# zx80_SD_12_smd_build006_8_STM32.net
KiCad netlist of a schematic drawn in EAGLE
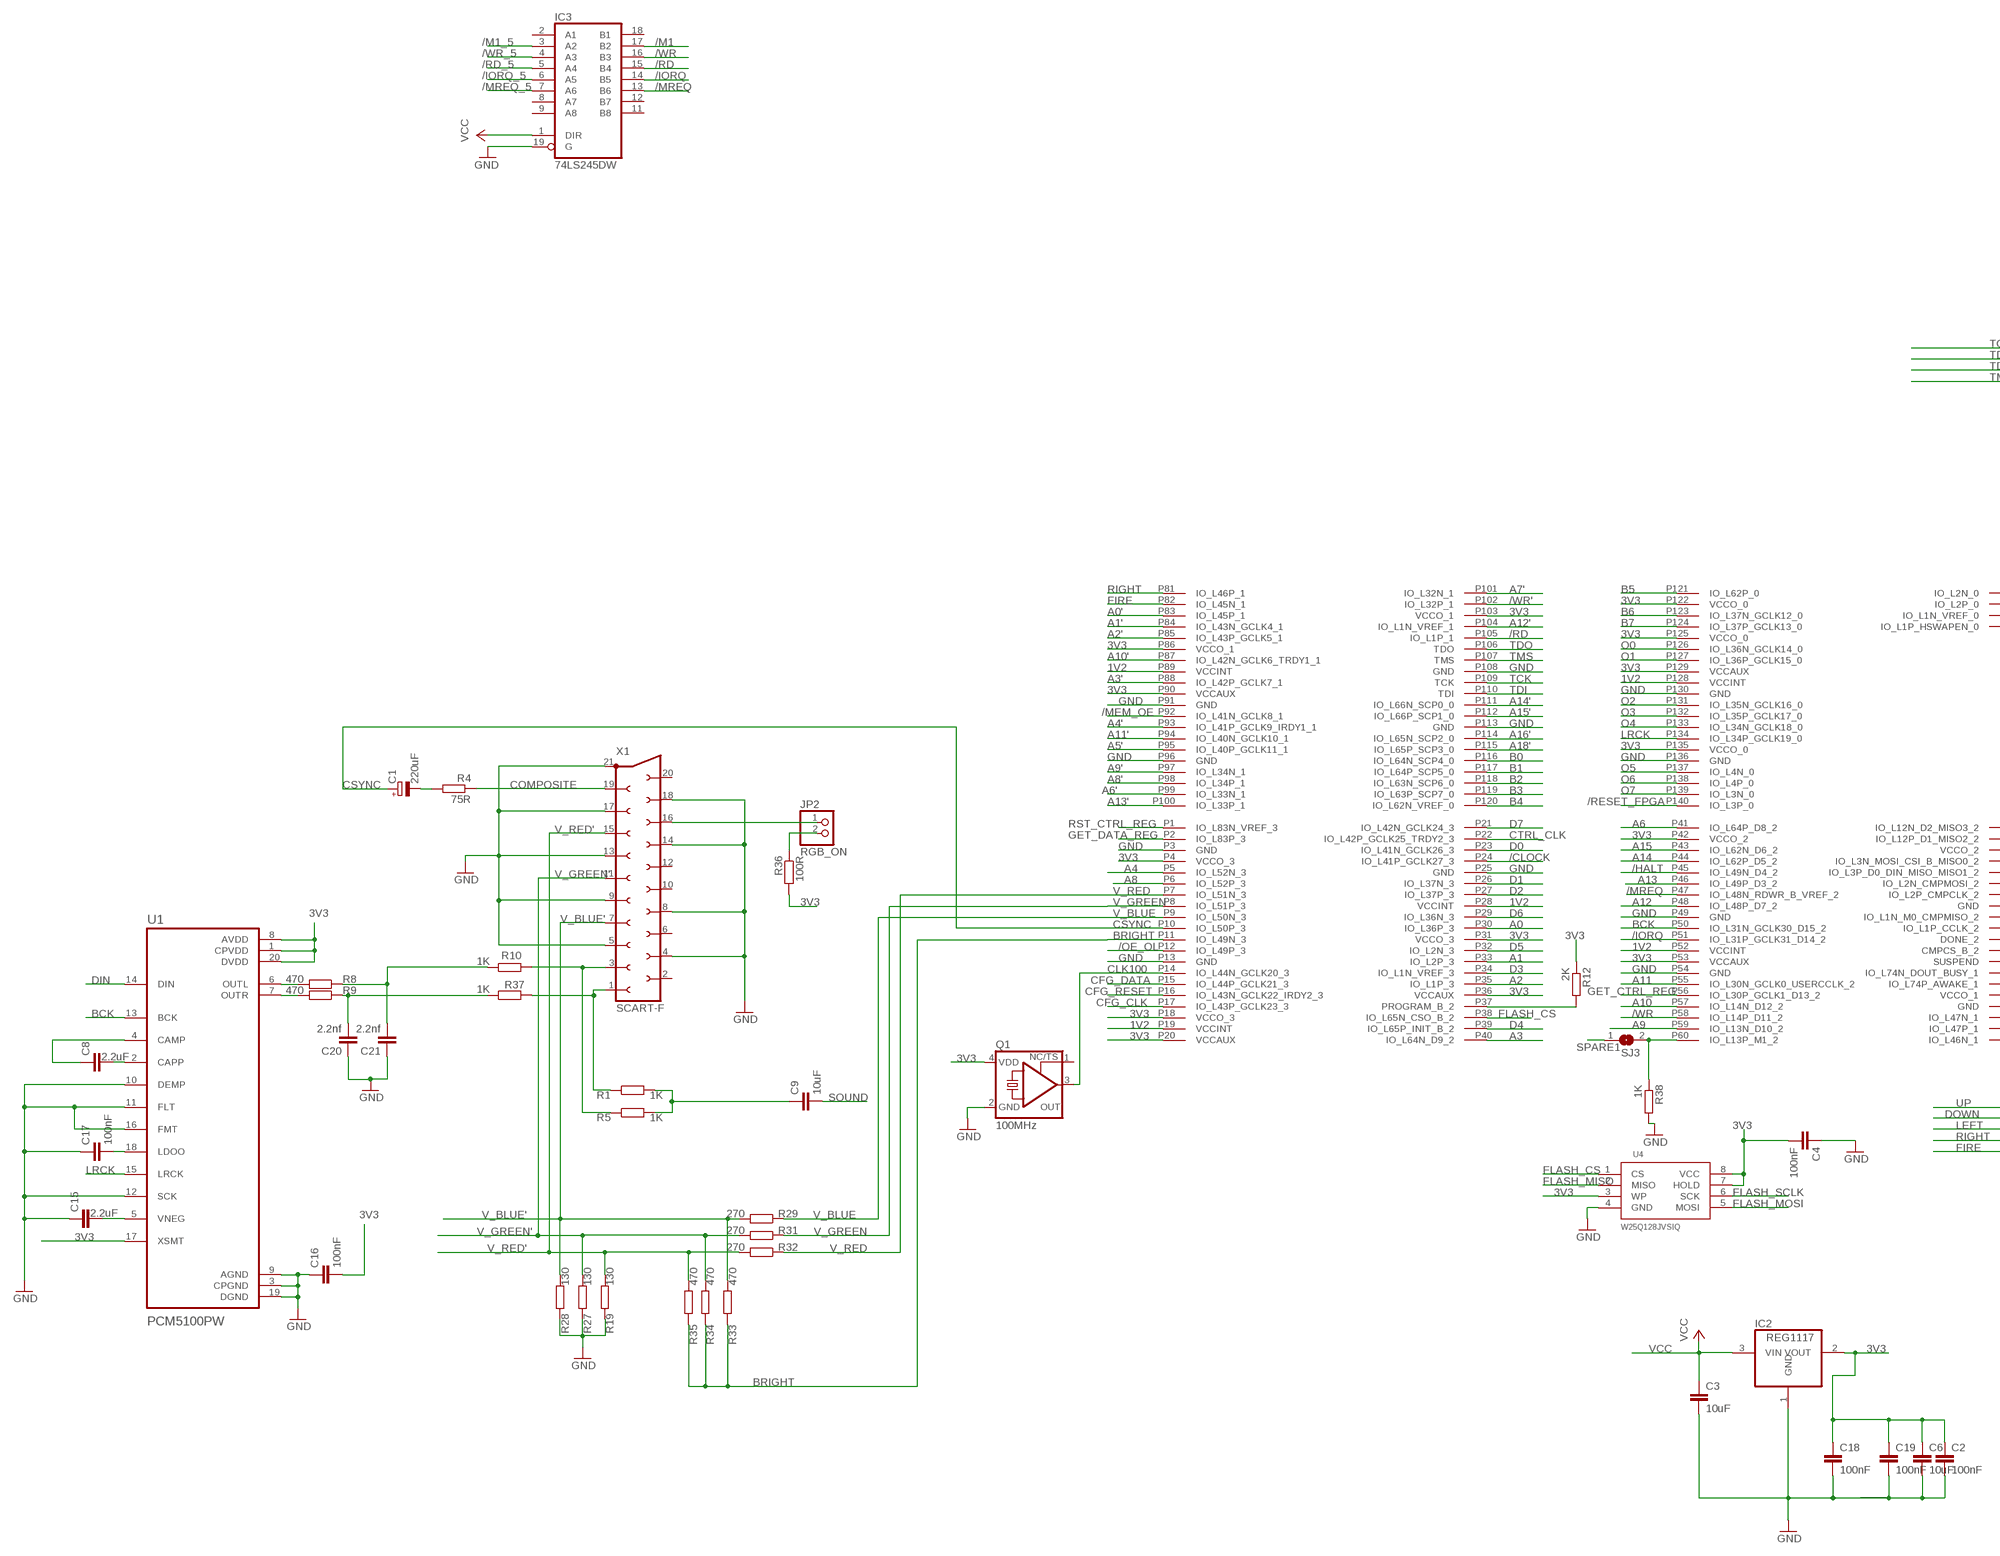
[diagram p0: schematic, sheet 1, part 1 of 2]
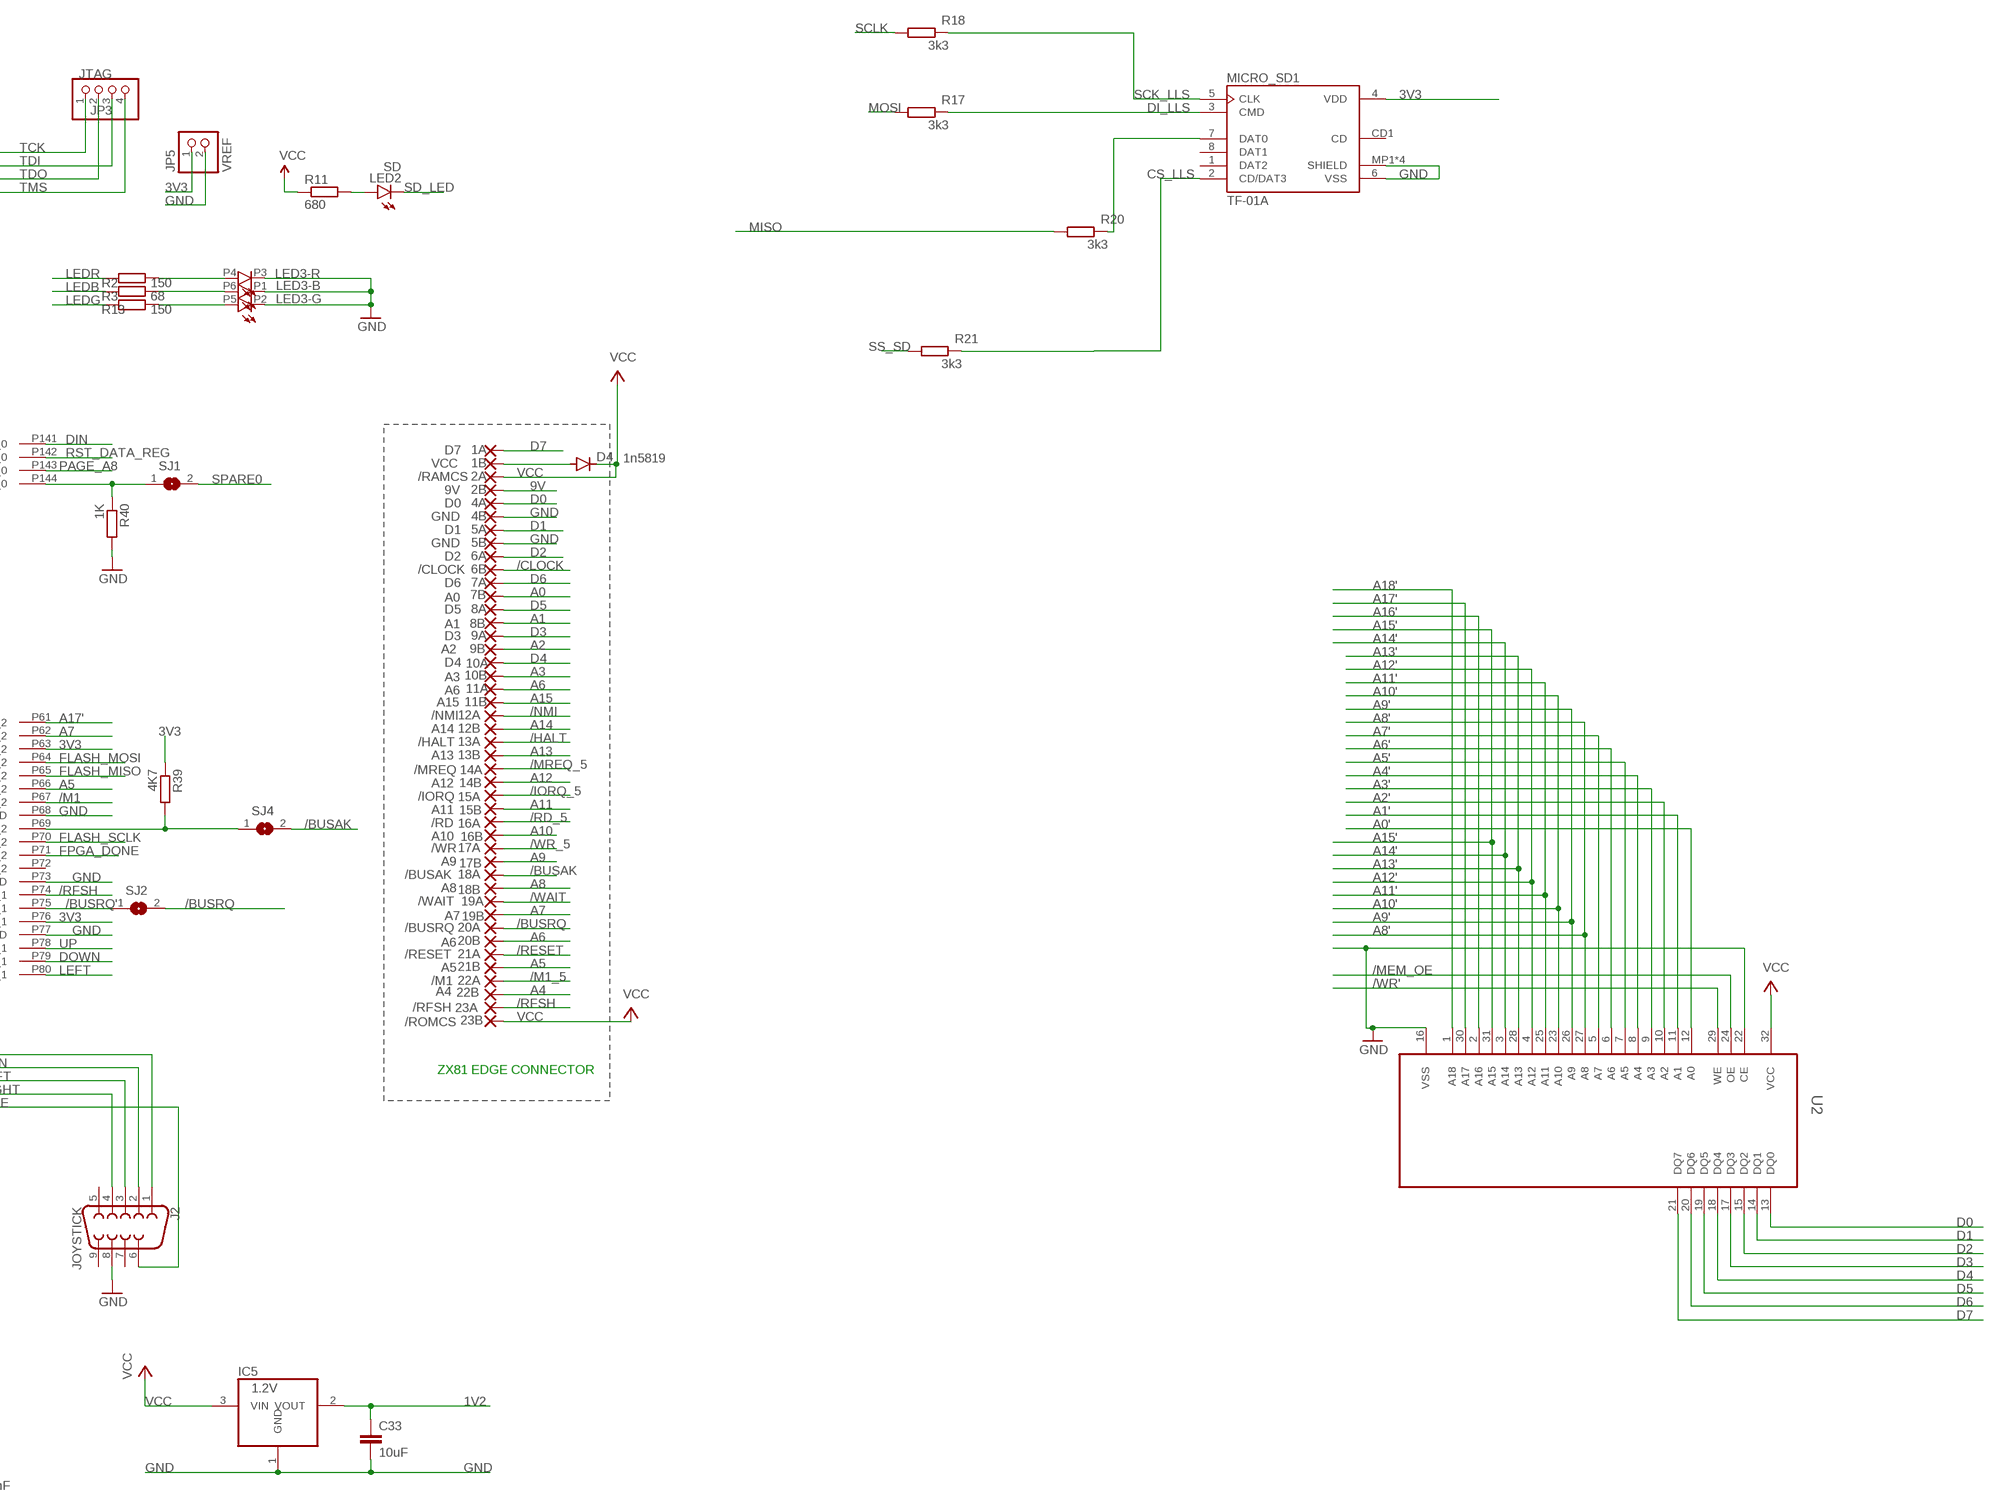
[diagram p1: schematic, sheet 1, part 2 of 2]
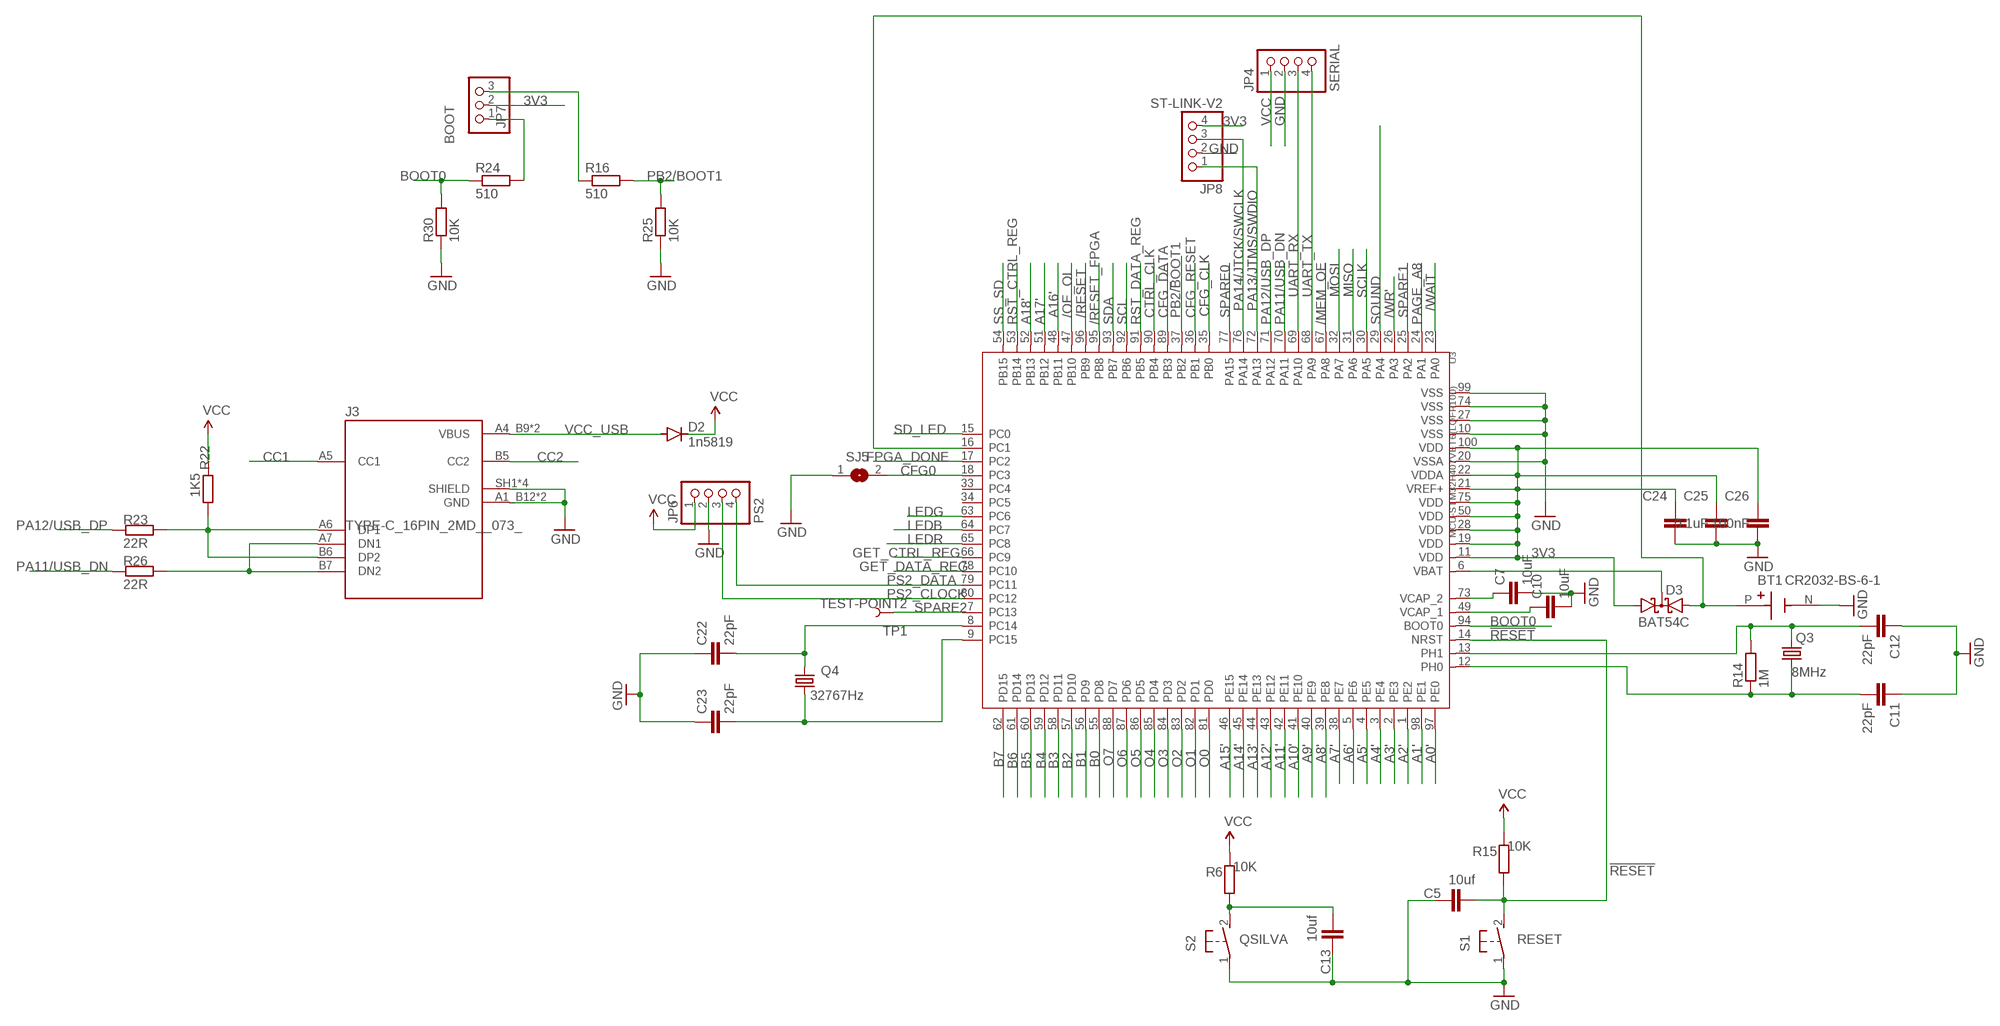
[diagram p2: schematic, sheet 2]

(export (version "E")
  (design (tool "Eeschema 10.0.6"))
  (components
    (comp (ref "1A")
      (value "D7")
      (footprint "eagle-import:EDGEPIN")
      (libsource (lib "eagle-import") (part "SMD2EDGEPIN"))
    )
    (comp (ref "1B")
      (value "VCC")
      (footprint "eagle-import:EDGEPIN")
      (libsource (lib "eagle-import") (part "SMD2EDGEPIN"))
    )
    (comp (ref "2A")
      (value "/RAMCS")
      (footprint "eagle-import:EDGEPIN")
      (libsource (lib "eagle-import") (part "SMD2EDGEPIN"))
    )
    (comp (ref "2B")
      (value "9V")
      (footprint "eagle-import:EDGEPIN")
      (libsource (lib "eagle-import") (part "SMD2EDGEPIN"))
    )
    (comp (ref "4A")
      (value "D0")
      (footprint "eagle-import:EDGEPIN")
      (libsource (lib "eagle-import") (part "SMD2EDGEPIN"))
    )
    (comp (ref "4B")
      (value "GND")
      (footprint "eagle-import:EDGEPIN")
      (libsource (lib "eagle-import") (part "SMD2EDGEPIN"))
    )
    (comp (ref "5A")
      (value "D1")
      (footprint "eagle-import:EDGEPIN")
      (libsource (lib "eagle-import") (part "SMD2EDGEPIN"))
    )
    (comp (ref "5B")
      (value "GND")
      (footprint "eagle-import:EDGEPIN")
      (libsource (lib "eagle-import") (part "SMD2EDGEPIN"))
    )
    (comp (ref "6A")
      (value "D2")
      (footprint "eagle-import:EDGEPIN")
      (libsource (lib "eagle-import") (part "SMD2EDGEPIN"))
    )
    (comp (ref "6B")
      (value "/CLOCK")
      (footprint "eagle-import:EDGEPIN")
      (libsource (lib "eagle-import") (part "SMD2EDGEPIN"))
    )
    (comp (ref "7A")
      (value "D6")
      (footprint "eagle-import:EDGEPIN")
      (libsource (lib "eagle-import") (part "SMD2EDGEPIN"))
    )
    (comp (ref "7B")
      (value "A0")
      (footprint "eagle-import:EDGEPIN")
      (libsource (lib "eagle-import") (part "SMD2EDGEPIN"))
    )
    (comp (ref "8A")
      (value "D5")
      (footprint "eagle-import:EDGEPIN")
      (libsource (lib "eagle-import") (part "SMD2EDGEPIN"))
    )
    (comp (ref "8B")
      (value "A1")
      (footprint "eagle-import:EDGEPIN")
      (libsource (lib "eagle-import") (part "SMD2EDGEPIN"))
    )
    (comp (ref "9A")
      (value "D3")
      (footprint "eagle-import:EDGEPIN")
      (libsource (lib "eagle-import") (part "SMD2EDGEPIN"))
    )
    (comp (ref "9B")
      (value "A2")
      (footprint "eagle-import:EDGEPIN")
      (libsource (lib "eagle-import") (part "SMD2EDGEPIN"))
    )
    (comp (ref "10A")
      (value "D4")
      (footprint "eagle-import:EDGEPIN")
      (libsource (lib "eagle-import") (part "SMD2EDGEPIN"))
    )
    (comp (ref "10B")
      (value "A3")
      (footprint "eagle-import:EDGEPIN")
      (libsource (lib "eagle-import") (part "SMD2EDGEPIN"))
    )
    (comp (ref "11A")
      (value "A6")
      (footprint "eagle-import:EDGEPIN")
      (libsource (lib "eagle-import") (part "SMD2EDGEPIN"))
    )
    (comp (ref "11B")
      (value "A15")
      (footprint "eagle-import:EDGEPIN")
      (libsource (lib "eagle-import") (part "SMD2EDGEPIN"))
    )
    (comp (ref "12A")
      (value "/NMI")
      (footprint "eagle-import:EDGEPIN")
      (libsource (lib "eagle-import") (part "SMD2EDGEPIN"))
    )
    (comp (ref "12B")
      (value "A14")
      (footprint "eagle-import:EDGEPIN")
      (libsource (lib "eagle-import") (part "SMD2EDGEPIN"))
    )
    (comp (ref "13A")
      (value "/HALT")
      (footprint "eagle-import:EDGEPIN")
      (libsource (lib "eagle-import") (part "SMD2EDGEPIN"))
    )
    (comp (ref "13B")
      (value "A13")
      (footprint "eagle-import:EDGEPIN")
      (libsource (lib "eagle-import") (part "SMD2EDGEPIN"))
    )
    (comp (ref "14A")
      (value "/MREQ")
      (footprint "eagle-import:EDGEPIN")
      (libsource (lib "eagle-import") (part "SMD2EDGEPIN"))
    )
    (comp (ref "14B")
      (value "A12")
      (footprint "eagle-import:EDGEPIN")
      (libsource (lib "eagle-import") (part "SMD2EDGEPIN"))
    )
    (comp (ref "15A")
      (value "/IORQ")
      (footprint "eagle-import:EDGEPIN")
      (libsource (lib "eagle-import") (part "SMD2EDGEPIN"))
    )
    (comp (ref "15B")
      (value "A11")
      (footprint "eagle-import:EDGEPIN")
      (libsource (lib "eagle-import") (part "SMD2EDGEPIN"))
    )
    (comp (ref "16A")
      (value "/RD")
      (footprint "eagle-import:EDGEPIN")
      (libsource (lib "eagle-import") (part "SMD2EDGEPIN"))
    )
    (comp (ref "16B")
      (value "A10")
      (footprint "eagle-import:EDGEPIN")
      (libsource (lib "eagle-import") (part "SMD2EDGEPIN"))
    )
    (comp (ref "17A")
      (value "/WR")
      (footprint "eagle-import:EDGEPIN")
      (libsource (lib "eagle-import") (part "SMD2EDGEPIN"))
    )
    (comp (ref "17B")
      (value "A9")
      (footprint "eagle-import:EDGEPIN")
      (libsource (lib "eagle-import") (part "SMD2EDGEPIN"))
    )
    (comp (ref "18A")
      (value "/BUSAK")
      (footprint "eagle-import:EDGEPIN")
      (libsource (lib "eagle-import") (part "SMD2EDGEPIN"))
    )
    (comp (ref "18B")
      (value "A8")
      (footprint "eagle-import:EDGEPIN")
      (libsource (lib "eagle-import") (part "SMD2EDGEPIN"))
    )
    (comp (ref "19A")
      (value "/WAIT")
      (footprint "eagle-import:EDGEPIN")
      (libsource (lib "eagle-import") (part "SMD2EDGEPIN"))
    )
    (comp (ref "19B")
      (value "A7")
      (footprint "eagle-import:EDGEPIN")
      (libsource (lib "eagle-import") (part "SMD2EDGEPIN"))
    )
    (comp (ref "20A")
      (value "/BUSRQ")
      (footprint "eagle-import:EDGEPIN")
      (libsource (lib "eagle-import") (part "SMD2EDGEPIN"))
    )
    (comp (ref "20B")
      (value "A6")
      (footprint "eagle-import:EDGEPIN")
      (libsource (lib "eagle-import") (part "SMD2EDGEPIN"))
    )
    (comp (ref "21A")
      (value "/RESET")
      (footprint "eagle-import:EDGEPIN")
      (libsource (lib "eagle-import") (part "SMD2EDGEPIN"))
    )
    (comp (ref "21B")
      (value "A5")
      (footprint "eagle-import:EDGEPIN")
      (libsource (lib "eagle-import") (part "SMD2EDGEPIN"))
    )
    (comp (ref "22A")
      (value "/M1")
      (footprint "eagle-import:EDGEPIN")
      (libsource (lib "eagle-import") (part "SMD2EDGEPIN"))
    )
    (comp (ref "22B")
      (value "A4")
      (footprint "eagle-import:EDGEPIN")
      (libsource (lib "eagle-import") (part "SMD2EDGEPIN"))
    )
    (comp (ref "23A")
      (value "/RFSH")
      (footprint "eagle-import:EDGEPIN")
      (libsource (lib "eagle-import") (part "SMD2EDGEPIN"))
    )
    (comp (ref "23B")
      (value "/ROMCS")
      (footprint "eagle-import:EDGEPIN")
      (libsource (lib "eagle-import") (part "SMD2EDGEPIN"))
    )
    (comp (ref "C1")
      (value "220uF")
      (footprint "eagle-import:UD-6,3X7,7_NICHICON")
      (libsource (lib "eagle-import") (part "CPOL-EUUD-6,3X7,7"))
    )
    (comp (ref "C2")
      (value "100nF")
      (footprint "eagle-import:C0402K")
      (libsource (lib "eagle-import") (part "C-EUC0402K"))
    )
    (comp (ref "C3")
      (value "10uF")
      (footprint "eagle-import:C0402K")
      (libsource (lib "eagle-import") (part "C-EUC0402K"))
    )
    (comp (ref "C4")
      (value "100nF")
      (footprint "eagle-import:C0402K")
      (libsource (lib "eagle-import") (part "C-EUC0402K"))
    )
    (comp (ref "C6")
      (value "10uF")
      (footprint "eagle-import:C0402K")
      (libsource (lib "eagle-import") (part "C-EUC0402K"))
    )
    (comp (ref "C8")
      (value "2.2uF")
      (footprint "eagle-import:C0402K")
      (libsource (lib "eagle-import") (part "C-EUC0402K"))
    )
    (comp (ref "C9")
      (value "10uF")
      (footprint "eagle-import:C0402K")
      (libsource (lib "eagle-import") (part "C-EUC0402K"))
    )
    (comp (ref "C15")
      (value "2.2uF")
      (footprint "eagle-import:C0402K")
      (libsource (lib "eagle-import") (part "C-EUC0402K"))
    )
    (comp (ref "C16")
      (value "100nF")
      (footprint "eagle-import:C0402K")
      (libsource (lib "eagle-import") (part "C-EUC0402K"))
    )
    (comp (ref "C17")
      (value "100nF")
      (footprint "eagle-import:C0402K")
      (libsource (lib "eagle-import") (part "C-EUC0402K"))
    )
    (comp (ref "C18")
      (value "100nF")
      (footprint "eagle-import:C0402K")
      (libsource (lib "eagle-import") (part "C-EUC0402K"))
    )
    (comp (ref "C19")
      (value "100nF")
      (footprint "eagle-import:C0402K")
      (libsource (lib "eagle-import") (part "C-EUC0402K"))
    )
    (comp (ref "C20")
      (value "2.2nf")
      (footprint "eagle-import:C0603K")
      (libsource (lib "eagle-import") (part "C-EUC0603K"))
    )
    (comp (ref "C21")
      (value "2.2nf")
      (footprint "eagle-import:C0603K")
      (libsource (lib "eagle-import") (part "C-EUC0603K"))
    )
    (comp (ref "C33")
      (value "10uF")
      (footprint "eagle-import:C0402K")
      (libsource (lib "eagle-import") (part "C-EUC0402K"))
    )
    (comp (ref "D4")
      (value "1n5819")
      (footprint "eagle-import:SOD323-W")
      (libsource (lib "eagle-import") (part "DIODE-SOD323-W"))
    )
    (comp (ref "IC2")
      (value "REG1117")
      (footprint "eagle-import:SOT223")
      (libsource (lib "eagle-import") (part "REG1117"))
    )
    (comp (ref "IC3")
      (value "74LS245DW")
      (footprint "eagle-import:SO20W")
      (libsource (lib "eagle-import") (part "74245DWLS"))
    )
    (comp (ref "IC5")
      (value "1.2V")
      (footprint "eagle-import:SOT223")
      (fields (field (name "MPN") "REG1117"))
      (libsource (lib "eagle-import") (part "REG1117"))
    )
    (comp (ref "J2")
      (value "JOYSTICK")
      (footprint "eagle-import:DB9_MALE")
      (libsource (lib "eagle-import") (part "DB9MALE"))
    )
    (comp (ref "JP2")
      (value "RGB_ON")
      (footprint "eagle-import:1X02")
      (libsource (lib "eagle-import") (part "PINHD-1X2"))
    )
    (comp (ref "JP3")
      (value "JTAG")
      (footprint "eagle-import:1X04")
      (libsource (lib "eagle-import") (part "PINHD-1X4"))
    )
    (comp (ref "JP5")
      (value "VREF")
      (footprint "eagle-import:1X02")
      (libsource (lib "eagle-import") (part "PINHD-1X2"))
    )
    (comp (ref "LED2")
      (value "SD")
      (footprint "eagle-import:CHIPLED_0805")
      (libsource (lib "eagle-import") (part "LEDCHIPLED_0805"))
    )
    (comp (ref "LED3")
      (value "STATUS")
      (footprint "eagle-import:3535-PLCC6")
      (libsource (lib "eagle-import") (part "3535RGB3535RGB"))
    )
    (comp (ref "MICRO_SD1")
      (value "TF-01A")
      (footprint "eagle-import:TF-01A")
      (fields (field (name "MF") "HRO Electronics Co., Ltd."))
      (libsource (lib "eagle-import") (part "TF-01A"))
    )
    (comp (ref "Q1")
      (value "100MHz")
      (footprint "eagle-import:3.2X2.5_KXO-V96")
      (libsource (lib "eagle-import") (part "KXO-PXO/XO-V96"))
    )
    (comp (ref "R1")
      (value "1K")
      (footprint "eagle-import:R0402")
      (libsource (lib "eagle-import") (part "R-EU_R0402"))
    )
    (comp (ref "R2")
      (value "150")
      (footprint "eagle-import:R0402")
      (libsource (lib "eagle-import") (part "R-EU_R0402"))
    )
    (comp (ref "R3")
      (value "68")
      (footprint "eagle-import:R0402")
      (libsource (lib "eagle-import") (part "R-EU_R0402"))
    )
    (comp (ref "R4")
      (value "75R")
      (footprint "eagle-import:R0402")
      (libsource (lib "eagle-import") (part "R-EU_R0402"))
    )
    (comp (ref "R5")
      (value "1K")
      (footprint "eagle-import:R0402")
      (libsource (lib "eagle-import") (part "R-EU_R0402"))
    )
    (comp (ref "R8")
      (value "470")
      (footprint "eagle-import:R0402")
      (libsource (lib "eagle-import") (part "R-EU_R0402"))
    )
    (comp (ref "R9")
      (value "470")
      (footprint "eagle-import:R0402")
      (libsource (lib "eagle-import") (part "R-EU_R0402"))
    )
    (comp (ref "R10")
      (value "1K")
      (footprint "eagle-import:R0402")
      (libsource (lib "eagle-import") (part "R-EU_R0402"))
    )
    (comp (ref "R11")
      (value "680")
      (footprint "eagle-import:R0402")
      (libsource (lib "eagle-import") (part "R-EU_R0402"))
    )
    (comp (ref "R12")
      (value "2K")
      (footprint "eagle-import:R0402")
      (libsource (lib "eagle-import") (part "R-EU_R0402"))
    )
    (comp (ref "R13")
      (value "150")
      (footprint "eagle-import:R0402")
      (libsource (lib "eagle-import") (part "R-EU_R0402"))
    )
    (comp (ref "R17")
      (value "3k3")
      (footprint "eagle-import:R0402")
      (libsource (lib "eagle-import") (part "R-EU_R0402"))
    )
    (comp (ref "R18")
      (value "3k3")
      (footprint "eagle-import:R0402")
      (libsource (lib "eagle-import") (part "R-EU_R0402"))
    )
    (comp (ref "R19")
      (value "130")
      (footprint "eagle-import:R0402")
      (libsource (lib "eagle-import") (part "R-EU_R0402"))
    )
    (comp (ref "R20")
      (value "3k3")
      (footprint "eagle-import:R0402")
      (libsource (lib "eagle-import") (part "R-EU_R0402"))
    )
    (comp (ref "R21")
      (value "3k3")
      (footprint "eagle-import:R0402")
      (libsource (lib "eagle-import") (part "R-EU_R0402"))
    )
    (comp (ref "R27")
      (value "130")
      (footprint "eagle-import:R0402")
      (libsource (lib "eagle-import") (part "R-EU_R0402"))
    )
    (comp (ref "R28")
      (value "130")
      (footprint "eagle-import:R0402")
      (libsource (lib "eagle-import") (part "R-EU_R0402"))
    )
    (comp (ref "R29")
      (value "270")
      (footprint "eagle-import:R0402")
      (libsource (lib "eagle-import") (part "R-EU_R0402"))
    )
    (comp (ref "R31")
      (value "270")
      (footprint "eagle-import:R0402")
      (libsource (lib "eagle-import") (part "R-EU_R0402"))
    )
    (comp (ref "R32")
      (value "270")
      (footprint "eagle-import:R0402")
      (libsource (lib "eagle-import") (part "R-EU_R0402"))
    )
    (comp (ref "R33")
      (value "470")
      (footprint "eagle-import:R0402")
      (libsource (lib "eagle-import") (part "R-EU_R0402"))
    )
    (comp (ref "R34")
      (value "470")
      (footprint "eagle-import:R0402")
      (libsource (lib "eagle-import") (part "R-EU_R0402"))
    )
    (comp (ref "R35")
      (value "470")
      (footprint "eagle-import:R0402")
      (libsource (lib "eagle-import") (part "R-EU_R0402"))
    )
    (comp (ref "R36")
      (value "100R")
      (footprint "eagle-import:R0402")
      (libsource (lib "eagle-import") (part "R-EU_R0402"))
    )
    (comp (ref "R37")
      (value "1K")
      (footprint "eagle-import:R0402")
      (libsource (lib "eagle-import") (part "R-EU_R0402"))
    )
    (comp (ref "R38")
      (value "1K")
      (footprint "eagle-import:R0402")
      (libsource (lib "eagle-import") (part "R-EU_R0402"))
    )
    (comp (ref "R39")
      (value "4K7")
      (footprint "eagle-import:R0402")
      (libsource (lib "eagle-import") (part "R-EU_R0402"))
    )
    (comp (ref "R40")
      (value "1K")
      (footprint "eagle-import:R0402")
      (libsource (lib "eagle-import") (part "R-EU_R0402"))
    )
    (comp (ref "SJ1") (value "SJ") (footprint "eagle-import:SJ") (libsource (lib "eagle-import") (part "SJ")))
    (comp (ref "SJ2") (value "SJ") (footprint "eagle-import:SJ") (libsource (lib "eagle-import") (part "SJ")))
    (comp (ref "SJ3") (value "SJ") (footprint "eagle-import:SJ") (libsource (lib "eagle-import") (part "SJ")))
    (comp (ref "SJ4") (value "SJ") (footprint "eagle-import:SJ") (libsource (lib "eagle-import") (part "SJ")))
    (comp (ref "U1")
      (value "PCM5100PW")
      (footprint "eagle-import:SOP65P640X120-20N")
      (fields (field (name "MF") "Texas Instruments"))
      (libsource (lib "eagle-import") (part "PCM5100PW"))
    )
    (comp (ref "U2")
      (value "AS6C4008")
      (footprint "eagle-import:SOP32-5")
      (libsource (lib "eagle-import") (part "AS6C4008-55SINSOP5"))
    )
    (comp (ref "U4")
      (value "W25Q128JVSIQ")
      (footprint "eagle-import:SO08-EIAJ")
      (libsource (lib "eagle-import") (part "SPI_FLASH-X25XXSMD1"))
    )
    (comp (ref "U6")
      (value "XC6SLX9-2TQG144C")
      (footprint "eagle-import:TQ144")
      (fields (field (name "MF") "Xilinx Inc."))
      (libsource (lib "eagle-import") (part "XC6SLX9-2TQG144C"))
    )
    (comp (ref "X1")
      (value "SCART-F")
      (footprint "eagle-import:SCART-F")
      (libsource (lib "eagle-import") (part "SCART-F"))
    )
    (comp (ref "BT1")
      (value "CR2032-BS-6-1")
      (footprint "eagle-import:BAT_CR2032-BS-6-1")
      (fields (field (name "MF") "Shenzhen Q&J Electronics Co. Ltd"))
      (libsource (lib "eagle-import") (part "CR2032-BS-6-1"))
    )
    (comp (ref "C5")
      (value "10uf")
      (footprint "eagle-import:C0402K")
      (libsource (lib "eagle-import") (part "C-EUC0402K"))
    )
    (comp (ref "C7")
      (value "10uF")
      (footprint "eagle-import:C0402K")
      (libsource (lib "eagle-import") (part "C-EUC0402K"))
    )
    (comp (ref "C10")
      (value "10uF")
      (footprint "eagle-import:C0402K")
      (libsource (lib "eagle-import") (part "C-EUC0402K"))
    )
    (comp (ref "C11")
      (value "22pF")
      (footprint "eagle-import:C0603")
      (libsource (lib "eagle-import") (part "C-EUC0603"))
    )
    (comp (ref "C12")
      (value "22pF")
      (footprint "eagle-import:C0603")
      (libsource (lib "eagle-import") (part "C-EUC0603"))
    )
    (comp (ref "C13")
      (value "10uf")
      (footprint "eagle-import:C0402K")
      (libsource (lib "eagle-import") (part "C-EUC0402K"))
    )
    (comp (ref "C22")
      (value "22pF")
      (footprint "eagle-import:C0603")
      (libsource (lib "eagle-import") (part "C-EUC0603"))
    )
    (comp (ref "C23")
      (value "22pF")
      (footprint "eagle-import:C0603")
      (libsource (lib "eagle-import") (part "C-EUC0603"))
    )
    (comp (ref "C24")
      (value "0.1uF")
      (footprint "eagle-import:C0402K")
      (libsource (lib "eagle-import") (part "C-EUC0402K"))
    )
    (comp (ref "C25")
      (value "0.1uF")
      (footprint "eagle-import:C0402K")
      (libsource (lib "eagle-import") (part "C-EUC0402K"))
    )
    (comp (ref "C26")
      (value "100nF")
      (footprint "eagle-import:C0402K")
      (libsource (lib "eagle-import") (part "C-EUC0402K"))
    )
    (comp (ref "D2")
      (value "1n5819")
      (footprint "eagle-import:SOD323-W")
      (libsource (lib "eagle-import") (part "DIODE-SOD323-W"))
    )
    (comp (ref "D3")
      (value "BAT54C")
      (footprint "eagle-import:SOT23")
      (libsource (lib "eagle-import") (part "BAT54C"))
    )
    (comp (ref "J3")
      (value "TYPE-C_16PIN_2MD__073_")
      (footprint "eagle-import:SHOUHAN_TYPE-C_16PIN_2MD__073_")
      (fields (field (name "MF") "Shouhan") (field (name "MP") "TYPE-C 16PIN 2MD (073)"))
      (libsource (lib "eagle-import") (part "TYPE-C_16PIN_2MD__073_"))
    )
    (comp (ref "JP4")
      (value "SERIAL")
      (footprint "eagle-import:1X04")
      (libsource (lib "eagle-import") (part "PINHD-1X4"))
    )
    (comp (ref "JP6")
      (value "PS2")
      (footprint "eagle-import:1X04")
      (libsource (lib "eagle-import") (part "PINHD-1X4"))
    )
    (comp (ref "JP7")
      (value "BOOT")
      (footprint "eagle-import:1X03")
      (libsource (lib "eagle-import") (part "PINHD-1X3"))
    )
    (comp (ref "JP8")
      (value "ST-LINK-V2")
      (footprint "eagle-import:1X04")
      (libsource (lib "eagle-import") (part "PINHD-1X4"))
    )
    (comp (ref "Q3")
      (value "8MHz")
      (footprint "eagle-import:3.2X2.5_KX-7")
      (libsource (lib "eagle-import") (part "KX-7"))
    )
    (comp (ref "Q4")
      (value "32767Hz")
      (footprint "eagle-import:3.2X1.5")
      (libsource (lib "eagle-import") (part "KX-327-NHT"))
    )
    (comp (ref "R6")
      (value "10K")
      (footprint "eagle-import:R0402")
      (libsource (lib "eagle-import") (part "R-EU_R0402"))
    )
    (comp (ref "R14")
      (value "1M")
      (footprint "eagle-import:R0402")
      (libsource (lib "eagle-import") (part "R-EU_R0402"))
    )
    (comp (ref "R15")
      (value "10K")
      (footprint "eagle-import:R0402")
      (libsource (lib "eagle-import") (part "R-EU_R0402"))
    )
    (comp (ref "R16")
      (value "510")
      (footprint "eagle-import:R0402")
      (libsource (lib "eagle-import") (part "R-EU_R0402"))
    )
    (comp (ref "R22")
      (value "1K5")
      (footprint "eagle-import:R0402")
      (libsource (lib "eagle-import") (part "R-EU_R0402"))
    )
    (comp (ref "R23")
      (value "22R")
      (footprint "eagle-import:R0402")
      (libsource (lib "eagle-import") (part "R-EU_R0402"))
    )
    (comp (ref "R24")
      (value "510")
      (footprint "eagle-import:R0402")
      (libsource (lib "eagle-import") (part "R-EU_R0402"))
    )
    (comp (ref "R25")
      (value "10K")
      (footprint "eagle-import:R0402")
      (libsource (lib "eagle-import") (part "R-EU_R0402"))
    )
    (comp (ref "R26")
      (value "22R")
      (footprint "eagle-import:R0402")
      (libsource (lib "eagle-import") (part "R-EU_R0402"))
    )
    (comp (ref "R30")
      (value "10K")
      (footprint "eagle-import:R0402")
      (libsource (lib "eagle-import") (part "R-EU_R0402"))
    )
    (comp (ref "S1")
      (value "RESET")
      (footprint "eagle-import:B3F-31XX")
      (fields (field (name "MPN") "B3F-3100"))
      (libsource (lib "eagle-import") (part "31-XX"))
    )
    (comp (ref "S2")
      (value "QSILVA")
      (footprint "eagle-import:B3F-31XX")
      (fields (field (name "MPN") "B3F-3100"))
      (libsource (lib "eagle-import") (part "31-XX"))
    )
    (comp (ref "SJ5")
      (value "SJ")
      (footprint "eagle-import:SJ")
      (libsource (lib "eagle-import") (part "jumper_41245853_SJ"))
    )
    (comp (ref "TP1")
      (value "TEST-POINT2")
      (footprint "eagle-import:PAD.02X.02")
      (libsource (lib "eagle-import") (part "TEST-POINT2"))
    )
    (comp (ref "U3")
      (value "MCU-STM32F407VET6(LQFP100)")
      (footprint "eagle-import:LQFP100-0.5-13.8X13.8MM")
      (fields (field (name "MF") "STMicroelectronics") (field (name "MP") "STM32F407VET6"))
      (libsource (lib "eagle-import") (part "MCU-STM32F407VET6(LQFP100)"))
    )
  )
  (nets
    (net (code "1") (name "1V2") (class "Default")
      (node (ref "C33") (pin "1") (pinfunction "1_1") (pintype "passive"))
      (node (ref "IC5") (pin "2") (pinfunction "VOUT_2") (pintype "output"))
      (node (ref "U6") (pin "P128") (pinfunction "VCCINT_P128") (pintype "bidirectional"))
      (node (ref "U6") (pin "P19") (pinfunction "VCCINT_P19") (pintype "bidirectional"))
      (node (ref "U6") (pin "P28") (pinfunction "VCCINT_P28") (pintype "bidirectional"))
      (node (ref "U6") (pin "P52") (pinfunction "VCCINT_P52") (pintype "bidirectional"))
      (node (ref "U6") (pin "P89") (pinfunction "VCCINT_P89") (pintype "bidirectional"))
    )
    (net (code "2") (name "3V3") (class "Default")
      (node (ref "C16") (pin "2") (pinfunction "2_2") (pintype "passive"))
      (node (ref "C18") (pin "1") (pinfunction "1_1") (pintype "passive"))
      (node (ref "C19") (pin "1") (pinfunction "1_1") (pintype "passive"))
      (node (ref "C2") (pin "1") (pinfunction "1_1") (pintype "passive"))
      (node (ref "C24") (pin "1") (pinfunction "1_1") (pintype "passive"))
      (node (ref "C25") (pin "1") (pinfunction "1_1") (pintype "passive"))
      (node (ref "C26") (pin "1") (pinfunction "1_1") (pintype "passive"))
      (node (ref "C4") (pin "2") (pinfunction "2_2") (pintype "passive"))
      (node (ref "C6") (pin "1") (pinfunction "1_1") (pintype "passive"))
      (node (ref "D3") (pin "1") (pinfunction "A1_1") (pintype "passive"))
      (node (ref "IC2") (pin "2") (pinfunction "VOUT_2") (pintype "output"))
      (node (ref "JP5") (pin "1") (pinfunction "1_1") (pintype "passive"))
      (node (ref "JP7") (pin "2") (pinfunction "2_2") (pintype "passive"))
      (node (ref "JP8") (pin "4") (pinfunction "4_4") (pintype "passive"))
      (node (ref "MICRO_SD1") (pin "4") (pinfunction "VDD_4") (pintype "power_in"))
      (node (ref "Q1") (pin "4") (pinfunction "VDD_4") (pintype "power_in"))
      (node (ref "R12") (pin "1") (pinfunction "1_1") (pintype "passive"))
      (node (ref "R36") (pin "2") (pinfunction "2_2") (pintype "passive"))
      (node (ref "R39") (pin "1") (pinfunction "1_1") (pintype "passive"))
      (node (ref "U1") (pin "1") (pinfunction "CPVDD_1") (pintype "power_in"))
      (node (ref "U1") (pin "17") (pinfunction "XSMT_17") (pintype "bidirectional"))
      (node (ref "U1") (pin "20") (pinfunction "DVDD_20") (pintype "power_in"))
      (node (ref "U1") (pin "8") (pinfunction "AVDD_8") (pintype "power_in"))
      (node (ref "U3") (pin "100") (pinfunction "VDD_100") (pintype "bidirectional"))
      (node (ref "U3") (pin "11") (pinfunction "VDD_11") (pintype "bidirectional"))
      (node (ref "U3") (pin "19") (pinfunction "VDD_19") (pintype "bidirectional"))
      (node (ref "U3") (pin "21") (pinfunction "VREF+_21") (pintype "bidirectional"))
      (node (ref "U3") (pin "22") (pinfunction "VDDA_22") (pintype "bidirectional"))
      (node (ref "U3") (pin "28") (pinfunction "VDD_28") (pintype "bidirectional"))
      (node (ref "U3") (pin "50") (pinfunction "VDD_50") (pintype "bidirectional"))
      (node (ref "U3") (pin "75") (pinfunction "VDD_75") (pintype "bidirectional"))
      (node (ref "U4") (pin "3") (pinfunction "WP_3") (pintype "bidirectional"))
      (node (ref "U4") (pin "7") (pinfunction "HOLD_7") (pintype "bidirectional"))
      (node (ref "U4") (pin "8") (pinfunction "VCC_8") (pintype "power_in"))
      (node (ref "U6") (pin "P103") (pinfunction "VCCO_1_P103") (pintype "bidirectional"))
      (node (ref "U6") (pin "P122") (pinfunction "VCCO_0_P122") (pintype "bidirectional"))
      (node (ref "U6") (pin "P125") (pinfunction "VCCO_0_P125") (pintype "bidirectional"))
      (node (ref "U6") (pin "P129") (pinfunction "VCCAUX_P129") (pintype "bidirectional"))
      (node (ref "U6") (pin "P135") (pinfunction "VCCO_0_P135") (pintype "bidirectional"))
      (node (ref "U6") (pin "P18") (pinfunction "VCCO_3_P18") (pintype "bidirectional"))
      (node (ref "U6") (pin "P20") (pinfunction "VCCAUX_P20") (pintype "bidirectional"))
      (node (ref "U6") (pin "P31") (pinfunction "VCCO_3_P31") (pintype "bidirectional"))
      (node (ref "U6") (pin "P36") (pinfunction "VCCAUX_P36") (pintype "bidirectional"))
      (node (ref "U6") (pin "P4") (pinfunction "VCCO_3_P4") (pintype "bidirectional"))
      (node (ref "U6") (pin "P42") (pinfunction "VCCO_2_P42") (pintype "bidirectional"))
      (node (ref "U6") (pin "P53") (pinfunction "VCCAUX_P53") (pintype "bidirectional"))
      (node (ref "U6") (pin "P63") (pinfunction "VCCO_2_P63") (pintype "bidirectional"))
      (node (ref "U6") (pin "P76") (pinfunction "VCCO_1_P76") (pintype "bidirectional"))
      (node (ref "U6") (pin "P86") (pinfunction "VCCO_1_P86") (pintype "bidirectional"))
      (node (ref "U6") (pin "P90") (pinfunction "VCCAUX_P90") (pintype "bidirectional"))
    )
    (net (code "3") (name "9V") (class "Default")
      (node (ref "2B") (pin "1") (pinfunction "P_1") (pintype "passive"))
    )
    (net (code "4") (name "A0") (class "Default")
      (node (ref "7B") (pin "1") (pinfunction "P_1") (pintype "passive"))
      (node (ref "U6") (pin "P30") (pinfunction "IO_L36P_3_P30") (pintype "bidirectional"))
    )
    (net (code "5") (name "A0'") (class "Default")
      (node (ref "U2") (pin "12") (pinfunction "A0_12") (pintype "input"))
      (node (ref "U3") (pin "97") (pinfunction "PE0_97") (pintype "bidirectional"))
      (node (ref "U6") (pin "P83") (pinfunction "IO_L45P_1_P83") (pintype "bidirectional"))
    )
    (net (code "6") (name "A1") (class "Default")
      (node (ref "8B") (pin "1") (pinfunction "P_1") (pintype "passive"))
      (node (ref "U6") (pin "P33") (pinfunction "IO_L2P_3_P33") (pintype "bidirectional"))
    )
    (net (code "7") (name "A1'") (class "Default")
      (node (ref "U2") (pin "11") (pinfunction "A1_11") (pintype "input"))
      (node (ref "U3") (pin "98") (pinfunction "PE1_98") (pintype "bidirectional"))
      (node (ref "U6") (pin "P84") (pinfunction "IO_L43N_GCLK4_1_P84") (pintype "bidirectional"))
    )
    (net (code "8") (name "A2") (class "Default")
      (node (ref "9B") (pin "1") (pinfunction "P_1") (pintype "passive"))
      (node (ref "U6") (pin "P35") (pinfunction "IO_L1P_3_P35") (pintype "bidirectional"))
    )
    (net (code "9") (name "A2'") (class "Default")
      (node (ref "U2") (pin "10") (pinfunction "A2_10") (pintype "input"))
      (node (ref "U3") (pin "1") (pinfunction "PE2_1") (pintype "bidirectional"))
      (node (ref "U6") (pin "P85") (pinfunction "IO_L43P_GCLK5_1_P85") (pintype "bidirectional"))
    )
    (net (code "10") (name "A3") (class "Default")
      (node (ref "10B") (pin "1") (pinfunction "P_1") (pintype "passive"))
      (node (ref "U6") (pin "P40") (pinfunction "IO_L64N_D9_2_P40") (pintype "bidirectional"))
    )
    (net (code "11") (name "A3'") (class "Default")
      (node (ref "U2") (pin "9") (pinfunction "A3_9") (pintype "input"))
      (node (ref "U3") (pin "2") (pinfunction "PE3_2") (pintype "bidirectional"))
      (node (ref "U6") (pin "P88") (pinfunction "IO_L42P_GCLK7_1_P88") (pintype "bidirectional"))
    )
    (net (code "12") (name "A4") (class "Default")
      (node (ref "22B") (pin "1") (pinfunction "P_1") (pintype "passive"))
      (node (ref "U6") (pin "P5") (pinfunction "IO_L52N_3_P5") (pintype "bidirectional"))
    )
    (net (code "13") (name "A4'") (class "Default")
      (node (ref "U2") (pin "8") (pinfunction "A4_8") (pintype "input"))
      (node (ref "U3") (pin "3") (pinfunction "PE4_3") (pintype "bidirectional"))
      (node (ref "U6") (pin "P93") (pinfunction "IO_L41P_GCLK9_IRDY1_1_P93") (pintype "bidirectional"))
    )
    (net (code "14") (name "A5") (class "Default")
      (node (ref "21B") (pin "1") (pinfunction "P_1") (pintype "passive"))
      (node (ref "U6") (pin "P66") (pinfunction "IO_L2N_CMPMOSI_2_P66") (pintype "bidirectional"))
    )
    (net (code "15") (name "A5'") (class "Default")
      (node (ref "U2") (pin "7") (pinfunction "A5_7") (pintype "input"))
      (node (ref "U3") (pin "4") (pinfunction "PE5_4") (pintype "bidirectional"))
      (node (ref "U6") (pin "P95") (pinfunction "IO_L40P_GCLK11_1_P95") (pintype "bidirectional"))
    )
    (net (code "16") (name "A6") (class "Default")
      (node (ref "11A") (pin "1") (pinfunction "P_1") (pintype "passive"))
      (node (ref "20B") (pin "1") (pinfunction "P_1") (pintype "passive"))
      (node (ref "U6") (pin "P41") (pinfunction "IO_L64P_D8_2_P41") (pintype "bidirectional"))
    )
    (net (code "17") (name "A6'") (class "Default")
      (node (ref "U2") (pin "6") (pinfunction "A6_6") (pintype "input"))
      (node (ref "U3") (pin "5") (pinfunction "PE6_5") (pintype "bidirectional"))
      (node (ref "U6") (pin "P99") (pinfunction "IO_L33N_1_P99") (pintype "bidirectional"))
    )
    (net (code "18") (name "A7") (class "Default")
      (node (ref "19B") (pin "1") (pinfunction "P_1") (pintype "passive"))
      (node (ref "U6") (pin "P62") (pinfunction "IO_L12P_D1_MISO2_2_P62") (pintype "bidirectional"))
    )
    (net (code "19") (name "A7'") (class "Default")
      (node (ref "U2") (pin "5") (pinfunction "A7_5") (pintype "input"))
      (node (ref "U3") (pin "38") (pinfunction "PE7_38") (pintype "bidirectional"))
      (node (ref "U6") (pin "P101") (pinfunction "IO_L32N_1_P101") (pintype "bidirectional"))
    )
    (net (code "20") (name "A8") (class "Default")
      (node (ref "18B") (pin "1") (pinfunction "P_1") (pintype "passive"))
      (node (ref "U6") (pin "P6") (pinfunction "IO_L52P_3_P6") (pintype "bidirectional"))
    )
    (net (code "21") (name "A8'") (class "Default")
      (node (ref "U2") (pin "27") (pinfunction "A8_27") (pintype "input"))
      (node (ref "U3") (pin "39") (pinfunction "PE8_39") (pintype "bidirectional"))
      (node (ref "U6") (pin "P98") (pinfunction "IO_L34P_1_P98") (pintype "bidirectional"))
    )
    (net (code "22") (name "A9") (class "Default")
      (node (ref "17B") (pin "1") (pinfunction "P_1") (pintype "passive"))
      (node (ref "U6") (pin "P59") (pinfunction "IO_L13N_D10_2_P59") (pintype "bidirectional"))
    )
    (net (code "23") (name "A9'") (class "Default")
      (node (ref "U2") (pin "26") (pinfunction "A9_26") (pintype "input"))
      (node (ref "U3") (pin "40") (pinfunction "PE9_40") (pintype "bidirectional"))
      (node (ref "U6") (pin "P97") (pinfunction "IO_L34N_1_P97") (pintype "bidirectional"))
    )
    (net (code "24") (name "A10") (class "Default")
      (node (ref "16B") (pin "1") (pinfunction "P_1") (pintype "passive"))
      (node (ref "U6") (pin "P57") (pinfunction "IO_L14N_D12_2_P57") (pintype "bidirectional"))
    )
    (net (code "25") (name "A10'") (class "Default")
      (node (ref "U2") (pin "23") (pinfunction "A10_23") (pintype "input"))
      (node (ref "U3") (pin "41") (pinfunction "PE10_41") (pintype "bidirectional"))
      (node (ref "U6") (pin "P87") (pinfunction "IO_L42N_GCLK6_TRDY1_1_P87") (pintype "bidirectional"))
    )
    (net (code "26") (name "A11") (class "Default")
      (node (ref "15B") (pin "1") (pinfunction "P_1") (pintype "passive"))
      (node (ref "U6") (pin "P55") (pinfunction "IO_L30N_GCLK0_USERCCLK_2_P55") (pintype "bidirectional"))
    )
    (net (code "27") (name "A11'") (class "Default")
      (node (ref "U2") (pin "25") (pinfunction "A11_25") (pintype "input"))
      (node (ref "U3") (pin "42") (pinfunction "PE11_42") (pintype "bidirectional"))
      (node (ref "U6") (pin "P94") (pinfunction "IO_L40N_GCLK10_1_P94") (pintype "bidirectional"))
    )
    (net (code "28") (name "A12") (class "Default")
      (node (ref "14B") (pin "1") (pinfunction "P_1") (pintype "passive"))
      (node (ref "U6") (pin "P48") (pinfunction "IO_L48P_D7_2_P48") (pintype "bidirectional"))
    )
    (net (code "29") (name "A12'") (class "Default")
      (node (ref "U2") (pin "4") (pinfunction "A12_4") (pintype "input"))
      (node (ref "U3") (pin "43") (pinfunction "PE12_43") (pintype "bidirectional"))
      (node (ref "U6") (pin "P104") (pinfunction "IO_L1N_VREF_1_P104") (pintype "bidirectional"))
    )
    (net (code "30") (name "A13") (class "Default")
      (node (ref "13B") (pin "1") (pinfunction "P_1") (pintype "passive"))
      (node (ref "U6") (pin "P46") (pinfunction "IO_L49P_D3_2_P46") (pintype "bidirectional"))
    )
    (net (code "31") (name "A13'") (class "Default")
      (node (ref "U2") (pin "28") (pinfunction "A13_28") (pintype "input"))
      (node (ref "U3") (pin "44") (pinfunction "PE13_44") (pintype "bidirectional"))
      (node (ref "U6") (pin "P100") (pinfunction "IO_L33P_1_P100") (pintype "bidirectional"))
    )
    (net (code "32") (name "A14") (class "Default")
      (node (ref "12B") (pin "1") (pinfunction "P_1") (pintype "passive"))
      (node (ref "U6") (pin "P44") (pinfunction "IO_L62P_D5_2_P44") (pintype "bidirectional"))
    )
    (net (code "33") (name "A14'") (class "Default")
      (node (ref "U2") (pin "3") (pinfunction "A14_3") (pintype "input"))
      (node (ref "U3") (pin "45") (pinfunction "PE14_45") (pintype "bidirectional"))
      (node (ref "U6") (pin "P111") (pinfunction "IO_L66N_SCP0_0_P111") (pintype "bidirectional"))
    )
    (net (code "34") (name "A15") (class "Default")
      (node (ref "11B") (pin "1") (pinfunction "P_1") (pintype "passive"))
      (node (ref "U6") (pin "P43") (pinfunction "IO_L62N_D6_2_P43") (pintype "bidirectional"))
    )
    (net (code "35") (name "A15'") (class "Default")
      (node (ref "U2") (pin "31") (pinfunction "A15_31") (pintype "input"))
      (node (ref "U3") (pin "46") (pinfunction "PE15_46") (pintype "bidirectional"))
      (node (ref "U6") (pin "P112") (pinfunction "IO_L66P_SCP1_0_P112") (pintype "bidirectional"))
    )
    (net (code "36") (name "A16'") (class "Default")
      (node (ref "U2") (pin "2") (pinfunction "A16_2") (pintype "input"))
      (node (ref "U3") (pin "48") (pinfunction "PB11_48") (pintype "bidirectional"))
      (node (ref "U6") (pin "P114") (pinfunction "IO_L65N_SCP2_0_P114") (pintype "bidirectional"))
    )
    (net (code "37") (name "A17'") (class "Default")
      (node (ref "U2") (pin "30") (pinfunction "A17_30") (pintype "input"))
      (node (ref "U3") (pin "51") (pinfunction "PB12_51") (pintype "bidirectional"))
      (node (ref "U6") (pin "P61") (pinfunction "IO_L12N_D2_MISO3_2_P61") (pintype "bidirectional"))
    )
    (net (code "38") (name "A18'") (class "Default")
      (node (ref "U2") (pin "1") (pinfunction "A18_1") (pintype "input"))
      (node (ref "U3") (pin "52") (pinfunction "PB13_52") (pintype "bidirectional"))
      (node (ref "U6") (pin "P115") (pinfunction "IO_L65P_SCP3_0_P115") (pintype "bidirectional"))
    )
    (net (code "39") (name "B0") (class "Default")
      (node (ref "U3") (pin "55") (pinfunction "PD8_55") (pintype "bidirectional"))
      (node (ref "U6") (pin "P116") (pinfunction "IO_L64N_SCP4_0_P116") (pintype "bidirectional"))
    )
    (net (code "40") (name "B1") (class "Default")
      (node (ref "U3") (pin "56") (pinfunction "PD9_56") (pintype "bidirectional"))
      (node (ref "U6") (pin "P117") (pinfunction "IO_L64P_SCP5_0_P117") (pintype "bidirectional"))
    )
    (net (code "41") (name "B2") (class "Default")
      (node (ref "U3") (pin "57") (pinfunction "PD10_57") (pintype "bidirectional"))
      (node (ref "U6") (pin "P118") (pinfunction "IO_L63N_SCP6_0_P118") (pintype "bidirectional"))
    )
    (net (code "42") (name "B3") (class "Default")
      (node (ref "U3") (pin "58") (pinfunction "PD11_58") (pintype "bidirectional"))
      (node (ref "U6") (pin "P119") (pinfunction "IO_L63P_SCP7_0_P119") (pintype "bidirectional"))
    )
    (net (code "43") (name "B4") (class "Default")
      (node (ref "U3") (pin "59") (pinfunction "PD12_59") (pintype "bidirectional"))
      (node (ref "U6") (pin "P120") (pinfunction "IO_L62N_VREF_0_P120") (pintype "bidirectional"))
    )
    (net (code "44") (name "B5") (class "Default")
      (node (ref "U3") (pin "60") (pinfunction "PD13_60") (pintype "bidirectional"))
      (node (ref "U6") (pin "P121") (pinfunction "IO_L62P_0_P121") (pintype "bidirectional"))
    )
    (net (code "45") (name "B6") (class "Default")
      (node (ref "U3") (pin "61") (pinfunction "PD14_61") (pintype "bidirectional"))
      (node (ref "U6") (pin "P123") (pinfunction "IO_L37N_GCLK12_0_P123") (pintype "bidirectional"))
    )
    (net (code "46") (name "B7") (class "Default")
      (node (ref "U3") (pin "62") (pinfunction "PD15_62") (pintype "bidirectional"))
      (node (ref "U6") (pin "P124") (pinfunction "IO_L37P_GCLK13_0_P124") (pintype "bidirectional"))
    )
    (net (code "47") (name "BCK") (class "Default")
      (node (ref "U1") (pin "13") (pinfunction "BCK_13") (pintype "bidirectional"))
      (node (ref "U6") (pin "P50") (pinfunction "IO_L31N_GCLK30_D15_2_P50") (pintype "bidirectional"))
    )
    (net (code "48") (name "BOOT0") (class "Default")
      (node (ref "R24") (pin "1") (pinfunction "1_1") (pintype "passive"))
      (node (ref "R30") (pin "2") (pinfunction "2_2") (pintype "passive"))
      (node (ref "U3") (pin "94") (pinfunction "BOOT0_94") (pintype "bidirectional"))
    )
    (net (code "49") (name "BRIGHT") (class "Default")
      (node (ref "R33") (pin "1") (pinfunction "1_1") (pintype "passive"))
      (node (ref "R34") (pin "1") (pinfunction "1_1") (pintype "passive"))
      (node (ref "R35") (pin "1") (pinfunction "1_1") (pintype "passive"))
      (node (ref "U6") (pin "P11") (pinfunction "IO_L49N_3_P11") (pintype "bidirectional"))
    )
    (net (code "50") (name "CC1") (class "Default")
      (node (ref "J3") (pin "A5") (pinfunction "CC1_A5") (pintype "bidirectional"))
    )
    (net (code "51") (name "CC2") (class "Default")
      (node (ref "J3") (pin "B5") (pinfunction "CC2_B5") (pintype "bidirectional"))
    )
    (net (code "52") (name "CFG0") (class "Default")
      (node (ref "SJ5") (pin "2") (pinfunction "2_2") (pintype "passive"))
      (node (ref "U3") (pin "18") (pinfunction "PC3_18") (pintype "bidirectional"))
    )
    (net (code "53") (name "CFG_CLK") (class "Default")
      (node (ref "U3") (pin "35") (pinfunction "PB0_35") (pintype "bidirectional"))
      (node (ref "U6") (pin "P17") (pinfunction "IO_L43P_GCLK23_3_P17") (pintype "bidirectional"))
    )
    (net (code "54") (name "CFG_DATA") (class "Default")
      (node (ref "U3") (pin "89") (pinfunction "PB3_89") (pintype "bidirectional"))
      (node (ref "U6") (pin "P15") (pinfunction "IO_L44P_GCLK21_3_P15") (pintype "bidirectional"))
    )
    (net (code "55") (name "CFG_RESET") (class "Default")
      (node (ref "U3") (pin "36") (pinfunction "PB1_36") (pintype "bidirectional"))
      (node (ref "U6") (pin "P16") (pinfunction "IO_L43N_GCLK22_IRDY2_3_P16") (pintype "bidirectional"))
    )
    (net (code "56") (name "CLK100") (class "Default")
      (node (ref "Q1") (pin "3") (pinfunction "OUT_3") (pintype "output"))
      (node (ref "U6") (pin "P14") (pinfunction "IO_L44N_GCLK20_3_P14") (pintype "bidirectional"))
    )
    (net (code "57") (name "COMPOSITE") (class "Default")
      (node (ref "R4") (pin "1") (pinfunction "1_1") (pintype "passive"))
      (node (ref "X1") (pin "19") (pinfunction "19_19") (pintype "passive"))
    )
    (net (code "58") (name "CSYNC") (class "Default")
      (node (ref "C1") (pin "+") (pinfunction "+_+") (pintype "passive"))
      (node (ref "U6") (pin "P10") (pinfunction "IO_L50P_3_P10") (pintype "bidirectional"))
    )
    (net (code "59") (name "CS_LLS") (class "Default")
      (node (ref "MICRO_SD1") (pin "2") (pinfunction "CD/DAT3_2") (pintype "bidirectional"))
      (node (ref "R21") (pin "2") (pinfunction "2_2") (pintype "passive"))
    )
    (net (code "60") (name "CTRL_CLK") (class "Default")
      (node (ref "U3") (pin "90") (pinfunction "PB4_90") (pintype "bidirectional"))
      (node (ref "U6") (pin "P22") (pinfunction "IO_L42P_GCLK25_TRDY2_3_P22") (pintype "bidirectional"))
    )
    (net (code "61") (name "D0") (class "Default")
      (node (ref "4A") (pin "1") (pinfunction "P_1") (pintype "passive"))
      (node (ref "U2") (pin "13") (pinfunction "DQ0_13") (pintype "output"))
      (node (ref "U6") (pin "P23") (pinfunction "IO_L41N_GCLK26_3_P23") (pintype "bidirectional"))
    )
    (net (code "62") (name "D1") (class "Default")
      (node (ref "5A") (pin "1") (pinfunction "P_1") (pintype "passive"))
      (node (ref "U2") (pin "14") (pinfunction "DQ1_14") (pintype "output"))
      (node (ref "U6") (pin "P26") (pinfunction "IO_L37N_3_P26") (pintype "bidirectional"))
    )
    (net (code "63") (name "D2") (class "Default")
      (node (ref "6A") (pin "1") (pinfunction "P_1") (pintype "passive"))
      (node (ref "U2") (pin "15") (pinfunction "DQ2_15") (pintype "output"))
      (node (ref "U6") (pin "P27") (pinfunction "IO_L37P_3_P27") (pintype "bidirectional"))
    )
    (net (code "64") (name "D3") (class "Default")
      (node (ref "9A") (pin "1") (pinfunction "P_1") (pintype "passive"))
      (node (ref "U2") (pin "17") (pinfunction "DQ3_17") (pintype "output"))
      (node (ref "U6") (pin "P34") (pinfunction "IO_L1N_VREF_3_P34") (pintype "bidirectional"))
    )
    (net (code "65") (name "D4") (class "Default")
      (node (ref "10A") (pin "1") (pinfunction "P_1") (pintype "passive"))
      (node (ref "U2") (pin "18") (pinfunction "DQ4_18") (pintype "output"))
      (node (ref "U6") (pin "P39") (pinfunction "IO_L65P_INIT_B_2_P39") (pintype "bidirectional"))
    )
    (net (code "66") (name "D5") (class "Default")
      (node (ref "8A") (pin "1") (pinfunction "P_1") (pintype "passive"))
      (node (ref "U2") (pin "19") (pinfunction "DQ5_19") (pintype "output"))
      (node (ref "U6") (pin "P32") (pinfunction "IO_L2N_3_P32") (pintype "bidirectional"))
    )
    (net (code "67") (name "D6") (class "Default")
      (node (ref "7A") (pin "1") (pinfunction "P_1") (pintype "passive"))
      (node (ref "U2") (pin "20") (pinfunction "DQ6_20") (pintype "output"))
      (node (ref "U6") (pin "P29") (pinfunction "IO_L36N_3_P29") (pintype "bidirectional"))
    )
    (net (code "68") (name "D7") (class "Default")
      (node (ref "1A") (pin "1") (pinfunction "P_1") (pintype "passive"))
      (node (ref "U2") (pin "21") (pinfunction "DQ7_21") (pintype "output"))
      (node (ref "U6") (pin "P21") (pinfunction "IO_L42N_GCLK24_3_P21") (pintype "bidirectional"))
    )
    (net (code "69") (name "DIN") (class "Default")
      (node (ref "U1") (pin "14") (pinfunction "DIN_14") (pintype "input"))
      (node (ref "U6") (pin "P141") (pinfunction "IO_L2N_0_P141") (pintype "bidirectional"))
    )
    (net (code "70") (name "DI_LLS") (class "Default")
      (node (ref "MICRO_SD1") (pin "3") (pinfunction "CMD_3") (pintype "bidirectional"))
      (node (ref "R17") (pin "2") (pinfunction "2_2") (pintype "passive"))
    )
    (net (code "71") (name "DOWN") (class "Default")
      (node (ref "J2") (pin "2") (pinfunction "2_2") (pintype "passive"))
      (node (ref "U6") (pin "P79") (pinfunction "IO_L47P_1_P79") (pintype "bidirectional"))
    )
    (net (code "72") (name "FIRE") (class "Default")
      (node (ref "J2") (pin "6") (pinfunction "6_6") (pintype "passive"))
      (node (ref "U6") (pin "P82") (pinfunction "IO_L45N_1_P82") (pintype "bidirectional"))
    )
    (net (code "73") (name "FLASH_CS") (class "Default")
      (node (ref "U4") (pin "1") (pinfunction "CS_1") (pintype "bidirectional"))
      (node (ref "U6") (pin "P38") (pinfunction "IO_L65N_CSO_B_2_P38") (pintype "bidirectional"))
    )
    (net (code "74") (name "FLASH_MISO") (class "Default")
      (node (ref "U4") (pin "2") (pinfunction "MISO_2") (pintype "bidirectional"))
      (node (ref "U6") (pin "P65") (pinfunction "IO_L3P_D0_DIN_MISO_MISO1_2_P65") (pintype "bidirectional"))
    )
    (net (code "75") (name "FLASH_MOSI") (class "Default")
      (node (ref "U4") (pin "5") (pinfunction "MOSI_5") (pintype "bidirectional"))
      (node (ref "U6") (pin "P64") (pinfunction "IO_L3N_MOSI_CSI_B_MISO0_2_P64") (pintype "bidirectional"))
    )
    (net (code "76") (name "FLASH_SCLK") (class "Default")
      (node (ref "U4") (pin "6") (pinfunction "SCK_6") (pintype "bidirectional"))
      (node (ref "U6") (pin "P70") (pinfunction "IO_L1P_CCLK_2_P70") (pintype "bidirectional"))
    )
    (net (code "77") (name "FPGA_DONE") (class "Default")
      (node (ref "U3") (pin "17") (pinfunction "PC2_17") (pintype "bidirectional"))
      (node (ref "U6") (pin "P71") (pinfunction "DONE_2_P71") (pintype "bidirectional"))
    )
    (net (code "78") (name "GET_CTRL_REG") (class "Default")
      (node (ref "U3") (pin "66") (pinfunction "PC9_66") (pintype "bidirectional"))
      (node (ref "U6") (pin "P56") (pinfunction "IO_L30P_GCLK1_D13_2_P56") (pintype "bidirectional"))
    )
    (net (code "79") (name "GET_DATA_REG") (class "Default")
      (node (ref "U3") (pin "78") (pinfunction "PC10_78") (pintype "bidirectional"))
      (node (ref "U6") (pin "P2") (pinfunction "IO_L83P_3_P2") (pintype "bidirectional"))
    )
    (net (code "80") (name "GND") (class "Default")
      (node (ref "4B") (pin "1") (pinfunction "P_1") (pintype "passive"))
      (node (ref "5B") (pin "1") (pinfunction "P_1") (pintype "passive"))
      (node (ref "BT1") (pin "N") (pinfunction "NEG_N") (pintype "passive"))
      (node (ref "C10") (pin "2") (pinfunction "2_2") (pintype "passive"))
      (node (ref "C11") (pin "1") (pinfunction "1_1") (pintype "passive"))
      (node (ref "C12") (pin "1") (pinfunction "1_1") (pintype "passive"))
      (node (ref "C13") (pin "1") (pinfunction "1_1") (pintype "passive"))
      (node (ref "C15") (pin "1") (pinfunction "1_1") (pintype "passive"))
      (node (ref "C16") (pin "1") (pinfunction "1_1") (pintype "passive"))
      (node (ref "C17") (pin "1") (pinfunction "1_1") (pintype "passive"))
      (node (ref "C18") (pin "2") (pinfunction "2_2") (pintype "passive"))
      (node (ref "C19") (pin "2") (pinfunction "2_2") (pintype "passive"))
      (node (ref "C2") (pin "2") (pinfunction "2_2") (pintype "passive"))
      (node (ref "C20") (pin "1") (pinfunction "1_1") (pintype "passive"))
      (node (ref "C21") (pin "1") (pinfunction "1_1") (pintype "passive"))
      (node (ref "C22") (pin "1") (pinfunction "1_1") (pintype "passive"))
      (node (ref "C23") (pin "1") (pinfunction "1_1") (pintype "passive"))
      (node (ref "C24") (pin "2") (pinfunction "2_2") (pintype "passive"))
      (node (ref "C25") (pin "2") (pinfunction "2_2") (pintype "passive"))
      (node (ref "C26") (pin "2") (pinfunction "2_2") (pintype "passive"))
      (node (ref "C3") (pin "2") (pinfunction "2_2") (pintype "passive"))
      (node (ref "C33") (pin "2") (pinfunction "2_2") (pintype "passive"))
      (node (ref "C4") (pin "1") (pinfunction "1_1") (pintype "passive"))
      (node (ref "C5") (pin "1") (pinfunction "1_1") (pintype "passive"))
      (node (ref "C6") (pin "2") (pinfunction "2_2") (pintype "passive"))
      (node (ref "C7") (pin "2") (pinfunction "2_2") (pintype "passive"))
      (node (ref "IC2") (pin "1") (pinfunction "GND_1") (pintype "power_in"))
      (node (ref "IC3") (pin "19") (pinfunction "G_19") (pintype "input"))
      (node (ref "IC5") (pin "1") (pinfunction "GND_1") (pintype "power_in"))
      (node (ref "J2") (pin "8") (pinfunction "8_8") (pintype "passive"))
      (node (ref "J3") (pin "A1_B12") (pinfunction "GND_A1_B12") (pintype "power_in"))
      (node (ref "J3") (pin "B1_A12") (pinfunction "GND_B1_A12") (pintype "power_in"))
      (node (ref "J3") (pin "SH1") (pinfunction "SHIELD_SH1") (pintype "passive"))
      (node (ref "J3") (pin "SH2") (pinfunction "SHIELD_SH2") (pintype "passive"))
      (node (ref "J3") (pin "SH3") (pinfunction "SHIELD_SH3") (pintype "passive"))
      (node (ref "J3") (pin "SH4") (pinfunction "SHIELD_SH4") (pintype "passive"))
      (node (ref "JP4") (pin "2") (pinfunction "2_2") (pintype "passive"))
      (node (ref "JP5") (pin "2") (pinfunction "2_2") (pintype "passive"))
      (node (ref "JP6") (pin "2") (pinfunction "2_2") (pintype "passive"))
      (node (ref "JP8") (pin "2") (pinfunction "2_2") (pintype "passive"))
      (node (ref "LED3") (pin "P1") (pinfunction "C_P1") (pintype "passive"))
      (node (ref "LED3") (pin "P2") (pinfunction "C_P2") (pintype "passive"))
      (node (ref "LED3") (pin "P3") (pinfunction "C_P3") (pintype "passive"))
      (node (ref "MICRO_SD1") (pin "6") (pinfunction "VSS_6") (pintype "power_in"))
      (node (ref "MICRO_SD1") (pin "MP1") (pinfunction "SHIELD_MP1") (pintype "power_in"))
      (node (ref "MICRO_SD1") (pin "MP2") (pinfunction "SHIELD_MP2") (pintype "power_in"))
      (node (ref "MICRO_SD1") (pin "MP3") (pinfunction "SHIELD_MP3") (pintype "power_in"))
      (node (ref "MICRO_SD1") (pin "MP4") (pinfunction "SHIELD_MP4") (pintype "power_in"))
      (node (ref "Q1") (pin "2") (pinfunction "GND_2") (pintype "power_in"))
      (node (ref "R19") (pin "2") (pinfunction "2_2") (pintype "passive"))
      (node (ref "R25") (pin "1") (pinfunction "1_1") (pintype "passive"))
      (node (ref "R27") (pin "2") (pinfunction "2_2") (pintype "passive"))
      (node (ref "R28") (pin "2") (pinfunction "2_2") (pintype "passive"))
      (node (ref "R30") (pin "1") (pinfunction "1_1") (pintype "passive"))
      (node (ref "R38") (pin "2") (pinfunction "2_2") (pintype "passive"))
      (node (ref "R40") (pin "2") (pinfunction "2_2") (pintype "passive"))
      (node (ref "S1") (pin "1") (pinfunction "P_1") (pintype "passive"))
      (node (ref "S2") (pin "1") (pinfunction "P_1") (pintype "passive"))
      (node (ref "SJ5") (pin "1") (pinfunction "1_1") (pintype "passive"))
      (node (ref "U1") (pin "10") (pinfunction "DEMP_10") (pintype "bidirectional"))
      (node (ref "U1") (pin "11") (pinfunction "FLT_11") (pintype "bidirectional"))
      (node (ref "U1") (pin "12") (pinfunction "SCK_12") (pintype "bidirectional"))
      (node (ref "U1") (pin "16") (pinfunction "FMT_16") (pintype "bidirectional"))
      (node (ref "U1") (pin "19") (pinfunction "DGND_19") (pintype "power_in"))
      (node (ref "U1") (pin "3") (pinfunction "CPGND_3") (pintype "power_in"))
      (node (ref "U1") (pin "9") (pinfunction "AGND_9") (pintype "power_in"))
      (node (ref "U2") (pin "16") (pinfunction "VSS_16") (pintype "output"))
      (node (ref "U2") (pin "22") (pinfunction "CE_22") (pintype "input"))
      (node (ref "U3") (pin "10") (pinfunction "VSS_10") (pintype "bidirectional"))
      (node (ref "U3") (pin "20") (pinfunction "VSSA_20") (pintype "bidirectional"))
      (node (ref "U3") (pin "27") (pinfunction "VSS_27") (pintype "bidirectional"))
      (node (ref "U3") (pin "74") (pinfunction "VSS_74") (pintype "bidirectional"))
      (node (ref "U3") (pin "99") (pinfunction "VSS_99") (pintype "bidirectional"))
      (node (ref "U4") (pin "4") (pinfunction "GND_4") (pintype "power_in"))
      (node (ref "U6") (pin "P108") (pinfunction "GND_P108") (pintype "bidirectional"))
      (node (ref "U6") (pin "P113") (pinfunction "GND_P113") (pintype "bidirectional"))
      (node (ref "U6") (pin "P13") (pinfunction "GND_P13") (pintype "bidirectional"))
      (node (ref "U6") (pin "P130") (pinfunction "GND_P130") (pintype "bidirectional"))
      (node (ref "U6") (pin "P136") (pinfunction "GND_P136") (pintype "bidirectional"))
      (node (ref "U6") (pin "P25") (pinfunction "GND_P25") (pintype "bidirectional"))
      (node (ref "U6") (pin "P3") (pinfunction "GND_P3") (pintype "bidirectional"))
      (node (ref "U6") (pin "P49") (pinfunction "GND_P49") (pintype "bidirectional"))
      (node (ref "U6") (pin "P54") (pinfunction "GND_P54") (pintype "bidirectional"))
      (node (ref "U6") (pin "P68") (pinfunction "GND_P68") (pintype "bidirectional"))
      (node (ref "U6") (pin "P73") (pinfunction "SUSPEND_P73") (pintype "bidirectional"))
      (node (ref "U6") (pin "P77") (pinfunction "GND_P77") (pintype "bidirectional"))
      (node (ref "U6") (pin "P91") (pinfunction "GND_P91") (pintype "bidirectional"))
      (node (ref "U6") (pin "P96") (pinfunction "GND_P96") (pintype "bidirectional"))
      (node (ref "X1") (pin "13") (pinfunction "13_13") (pintype "passive"))
      (node (ref "X1") (pin "14") (pinfunction "14_14") (pintype "passive"))
      (node (ref "X1") (pin "17") (pinfunction "17_17") (pintype "passive"))
      (node (ref "X1") (pin "18") (pinfunction "18_18") (pintype "passive"))
      (node (ref "X1") (pin "21") (pinfunction "21_21") (pintype "passive"))
      (node (ref "X1") (pin "4") (pinfunction "4_4") (pintype "passive"))
      (node (ref "X1") (pin "5") (pinfunction "5_5") (pintype "passive"))
      (node (ref "X1") (pin "8") (pinfunction "8_8") (pintype "passive"))
      (node (ref "X1") (pin "9") (pinfunction "9_9") (pintype "passive"))
    )
    (net (code "81") (name "LEDB") (class "Default")
      (node (ref "R3") (pin "1") (pinfunction "1_1") (pintype "passive"))
      (node (ref "U3") (pin "64") (pinfunction "PC7_64") (pintype "bidirectional"))
    )
    (net (code "82") (name "LEDG") (class "Default")
      (node (ref "R13") (pin "1") (pinfunction "1_1") (pintype "passive"))
      (node (ref "U3") (pin "63") (pinfunction "PC6_63") (pintype "bidirectional"))
    )
    (net (code "83") (name "LEDR") (class "Default")
      (node (ref "R2") (pin "1") (pinfunction "1_1") (pintype "passive"))
      (node (ref "U3") (pin "65") (pinfunction "PC8_65") (pintype "bidirectional"))
    )
    (net (code "84") (name "LEFT") (class "Default")
      (node (ref "J2") (pin "3") (pinfunction "3_3") (pintype "passive"))
      (node (ref "U6") (pin "P80") (pinfunction "IO_L46N_1_P80") (pintype "bidirectional"))
    )
    (net (code "85") (name "LRCK") (class "Default")
      (node (ref "U1") (pin "15") (pinfunction "LRCK_15") (pintype "bidirectional"))
      (node (ref "U6") (pin "P134") (pinfunction "IO_L34P_GCLK19_0_P134") (pintype "bidirectional"))
    )
    (net (code "86") (name "MISO") (class "Default")
      (node (ref "R20") (pin "1") (pinfunction "1_1") (pintype "passive"))
      (node (ref "U3") (pin "31") (pinfunction "PA6_31") (pintype "bidirectional"))
    )
    (net (code "87") (name "MOSI") (class "Default")
      (node (ref "R17") (pin "1") (pinfunction "1_1") (pintype "passive"))
      (node (ref "U3") (pin "32") (pinfunction "PA7_32") (pintype "bidirectional"))
    )
    (net (code "88") (name "Net-(1B-P)") (class "Default")
      (node (ref "1B") (pin "1") (pinfunction "P_1") (pintype "passive"))
      (node (ref "D4") (pin "A") (pinfunction "A_A") (pintype "passive"))
    )
    (net (code "89") (name "Net-(BT1-POS)") (class "Default")
      (node (ref "BT1") (pin "P") (pinfunction "POS_P") (pintype "passive"))
      (node (ref "D3") (pin "2") (pinfunction "A2_2") (pintype "passive"))
      (node (ref "U3") (pin "16") (pinfunction "PC1_16") (pintype "bidirectional"))
    )
    (net (code "90") (name "Net-(C1-Pad-)") (class "Default")
      (node (ref "C1") (pin "-") (pinfunction "-_-") (pintype "passive"))
      (node (ref "R4") (pin "2") (pinfunction "2_2") (pintype "passive"))
    )
    (net (code "91") (name "Net-(C9-Pad1)") (class "Default")
      (node (ref "C9") (pin "1") (pinfunction "1_1") (pintype "passive"))
      (node (ref "R1") (pin "2") (pinfunction "2_2") (pintype "passive"))
      (node (ref "R5") (pin "2") (pinfunction "2_2") (pintype "passive"))
    )
    (net (code "92") (name "Net-(C20-Pad2)") (class "Default")
      (node (ref "C20") (pin "2") (pinfunction "2_2") (pintype "passive"))
      (node (ref "R37") (pin "1") (pinfunction "1_1") (pintype "passive"))
      (node (ref "R9") (pin "1") (pinfunction "1_1") (pintype "passive"))
    )
    (net (code "93") (name "Net-(C21-Pad2)") (class "Default")
      (node (ref "C21") (pin "2") (pinfunction "2_2") (pintype "passive"))
      (node (ref "R10") (pin "1") (pinfunction "1_1") (pintype "passive"))
      (node (ref "R8") (pin "1") (pinfunction "1_1") (pintype "passive"))
    )
    (net (code "94") (name "Net-(D3-CC)") (class "Default")
      (node (ref "D3") (pin "3") (pinfunction "CC_3") (pintype "passive"))
      (node (ref "U3") (pin "6") (pinfunction "VBAT_6") (pintype "bidirectional"))
    )
    (net (code "95") (name "Net-(J3-DN1)") (class "Default")
      (node (ref "J3") (pin "A7") (pinfunction "DN1_A7") (pintype "bidirectional"))
      (node (ref "J3") (pin "B7") (pinfunction "DN2_B7") (pintype "bidirectional"))
      (node (ref "R26") (pin "1") (pinfunction "1_1") (pintype "passive"))
    )
    (net (code "96") (name "Net-(J3-DP1)") (class "Default")
      (node (ref "J3") (pin "A6") (pinfunction "DP1_A6") (pintype "bidirectional"))
      (node (ref "J3") (pin "B6") (pinfunction "DP2_B6") (pintype "bidirectional"))
      (node (ref "R22") (pin "1") (pinfunction "1_1") (pintype "passive"))
      (node (ref "R23") (pin "1") (pinfunction "1_1") (pintype "passive"))
    )
    (net (code "97") (name "Net-(JP2-Pad1)") (class "Default")
      (node (ref "JP2") (pin "1") (pinfunction "1_1") (pintype "passive"))
      (node (ref "X1") (pin "16") (pinfunction "16_16") (pintype "passive"))
    )
    (net (code "98") (name "Net-(JP2-Pad2)") (class "Default")
      (node (ref "JP2") (pin "2") (pinfunction "2_2") (pintype "passive"))
      (node (ref "R36") (pin "1") (pinfunction "1_1") (pintype "passive"))
    )
    (net (code "99") (name "Net-(JP7-Pad1)") (class "Default")
      (node (ref "JP7") (pin "1") (pinfunction "1_1") (pintype "passive"))
      (node (ref "R24") (pin "2") (pinfunction "2_2") (pintype "passive"))
    )
    (net (code "100") (name "Net-(JP7-Pad3)") (class "Default")
      (node (ref "JP7") (pin "3") (pinfunction "3_3") (pintype "passive"))
      (node (ref "R16") (pin "1") (pinfunction "1_1") (pintype "passive"))
    )
    (net (code "101") (name "Net-(LED2-PadA)") (class "Default")
      (node (ref "LED2") (pin "A") (pinfunction "A_A") (pintype "passive"))
      (node (ref "R11") (pin "2") (pinfunction "2_2") (pintype "passive"))
    )
    (net (code "102") (name "Net-(LED3A-A)") (class "Default")
      (node (ref "LED3") (pin "P6") (pinfunction "A_P6") (pintype "passive"))
      (node (ref "R3") (pin "2") (pinfunction "2_2") (pintype "passive"))
    )
    (net (code "103") (name "Net-(LED3B-A)") (class "Default")
      (node (ref "LED3") (pin "P5") (pinfunction "A_P5") (pintype "passive"))
      (node (ref "R13") (pin "2") (pinfunction "2_2") (pintype "passive"))
    )
    (net (code "104") (name "Net-(LED3C-A)") (class "Default")
      (node (ref "LED3") (pin "P4") (pinfunction "A_P4") (pintype "passive"))
      (node (ref "R2") (pin "2") (pinfunction "2_2") (pintype "passive"))
    )
    (net (code "105") (name "Net-(MICRO_SD1-DAT0)") (class "Default")
      (node (ref "MICRO_SD1") (pin "7") (pinfunction "DAT0_7") (pintype "bidirectional"))
      (node (ref "R20") (pin "2") (pinfunction "2_2") (pintype "passive"))
    )
    (net (code "106") (name "Net-(Q3-2)") (class "Default")
      (node (ref "C12") (pin "2") (pinfunction "2_2") (pintype "passive"))
      (node (ref "Q3") (pin "3") (pinfunction "2_3") (pintype "passive"))
      (node (ref "R14") (pin "2") (pinfunction "2_2") (pintype "passive"))
      (node (ref "U3") (pin "13") (pinfunction "PH1_13") (pintype "bidirectional"))
    )
    (net (code "107") (name "Net-(R1-Pad1)") (class "Default")
      (node (ref "R1") (pin "1") (pinfunction "1_1") (pintype "passive"))
      (node (ref "R37") (pin "2") (pinfunction "2_2") (pintype "passive"))
      (node (ref "X1") (pin "1") (pinfunction "1_1") (pintype "passive"))
    )
    (net (code "108") (name "Net-(R10-Pad2)") (class "Default")
      (node (ref "R10") (pin "2") (pinfunction "2_2") (pintype "passive"))
      (node (ref "R5") (pin "1") (pinfunction "1_1") (pintype "passive"))
      (node (ref "X1") (pin "3") (pinfunction "3_3") (pintype "passive"))
    )
    (net (code "109") (name "Net-(S2-S)") (class "Default")
      (node (ref "C13") (pin "2") (pinfunction "2_2") (pintype "passive"))
      (node (ref "R6") (pin "1") (pinfunction "1_1") (pintype "passive"))
      (node (ref "S2") (pin "2") (pinfunction "S_2") (pintype "passive"))
    )
    (net (code "110") (name "Net-(U1-CAMP)") (class "Default")
      (node (ref "C8") (pin "1") (pinfunction "1_1") (pintype "passive"))
      (node (ref "U1") (pin "4") (pinfunction "CAMP_4") (pintype "bidirectional"))
    )
    (net (code "111") (name "Net-(U1-CAPP)") (class "Default")
      (node (ref "C8") (pin "2") (pinfunction "2_2") (pintype "passive"))
      (node (ref "U1") (pin "2") (pinfunction "CAPP_2") (pintype "bidirectional"))
    )
    (net (code "112") (name "Net-(U1-LDOO)") (class "Default")
      (node (ref "C17") (pin "2") (pinfunction "2_2") (pintype "passive"))
      (node (ref "U1") (pin "18") (pinfunction "LDOO_18") (pintype "bidirectional"))
    )
    (net (code "113") (name "Net-(U1-OUTL)") (class "Default")
      (node (ref "R8") (pin "2") (pinfunction "2_2") (pintype "passive"))
      (node (ref "U1") (pin "6") (pinfunction "OUTL_6") (pintype "output"))
    )
    (net (code "114") (name "Net-(U1-OUTR)") (class "Default")
      (node (ref "R9") (pin "2") (pinfunction "2_2") (pintype "passive"))
      (node (ref "U1") (pin "7") (pinfunction "OUTR_7") (pintype "output"))
    )
    (net (code "115") (name "Net-(U1-VNEG)") (class "Default")
      (node (ref "C15") (pin "2") (pinfunction "2_2") (pintype "passive"))
      (node (ref "U1") (pin "5") (pinfunction "VNEG_5") (pintype "bidirectional"))
    )
    (net (code "116") (name "Net-(U3-PC14)") (class "Default")
      (node (ref "C22") (pin "2") (pinfunction "2_2") (pintype "passive"))
      (node (ref "Q4") (pin "2") (pinfunction "2_2") (pintype "passive"))
      (node (ref "U3") (pin "8") (pinfunction "PC14_8") (pintype "bidirectional"))
    )
    (net (code "117") (name "Net-(U3-PC15)") (class "Default")
      (node (ref "C23") (pin "2") (pinfunction "2_2") (pintype "passive"))
      (node (ref "Q4") (pin "1") (pinfunction "1_1") (pintype "passive"))
      (node (ref "U3") (pin "9") (pinfunction "PC15_9") (pintype "bidirectional"))
    )
    (net (code "118") (name "Net-(U3-PH0)") (class "Default")
      (node (ref "C11") (pin "2") (pinfunction "2_2") (pintype "passive"))
      (node (ref "Q3") (pin "1") (pinfunction "1_1") (pintype "passive"))
      (node (ref "R14") (pin "1") (pinfunction "1_1") (pintype "passive"))
      (node (ref "U3") (pin "12") (pinfunction "PH0_12") (pintype "bidirectional"))
    )
    (net (code "119") (name "Net-(U3-VCAP_1)") (class "Default")
      (node (ref "C10") (pin "1") (pinfunction "1_1") (pintype "passive"))
      (node (ref "U3") (pin "49") (pinfunction "VCAP_1_49") (pintype "bidirectional"))
    )
    (net (code "120") (name "Net-(U3-VCAP_2)") (class "Default")
      (node (ref "C7") (pin "1") (pinfunction "1_1") (pintype "passive"))
      (node (ref "U3") (pin "73") (pinfunction "VCAP_2_73") (pintype "bidirectional"))
    )
    (net (code "121") (name "Net-(U6-IO_L1N_M0_CMPMISO_2)") (class "Default")
      (node (ref "R39") (pin "2") (pinfunction "2_2") (pintype "passive"))
      (node (ref "SJ4") (pin "1") (pinfunction "1_1") (pintype "passive"))
      (node (ref "U6") (pin "P69") (pinfunction "IO_L1N_M0_CMPMISO_2_P69") (pintype "bidirectional"))
    )
    (net (code "122") (name "Net-(U6-IO_L1P_HSWAPEN_0)") (class "Default")
      (node (ref "R40") (pin "1") (pinfunction "1_1") (pintype "passive"))
      (node (ref "SJ1") (pin "1") (pinfunction "1_1") (pintype "passive"))
      (node (ref "U6") (pin "P144") (pinfunction "IO_L1P_HSWAPEN_0_P144") (pintype "bidirectional"))
    )
    (net (code "123") (name "Net-(U6-IO_L13P_M1_2)") (class "Default")
      (node (ref "R38") (pin "1") (pinfunction "1_1") (pintype "passive"))
      (node (ref "SJ3") (pin "2") (pinfunction "2_2") (pintype "passive"))
      (node (ref "U6") (pin "P60") (pinfunction "IO_L13P_M1_2_P60") (pintype "bidirectional"))
    )
    (net (code "124") (name "Net-(U6-PROGRAM_B_2)") (class "Default")
      (node (ref "R12") (pin "2") (pinfunction "2_2") (pintype "passive"))
      (node (ref "U6") (pin "P37") (pinfunction "PROGRAM_B_2_P37") (pintype "bidirectional"))
    )
    (net (code "125") (name "O0") (class "Default")
      (node (ref "U3") (pin "81") (pinfunction "PD0_81") (pintype "bidirectional"))
      (node (ref "U6") (pin "P126") (pinfunction "IO_L36N_GCLK14_0_P126") (pintype "bidirectional"))
    )
    (net (code "126") (name "O1") (class "Default")
      (node (ref "U3") (pin "82") (pinfunction "PD1_82") (pintype "bidirectional"))
      (node (ref "U6") (pin "P127") (pinfunction "IO_L36P_GCLK15_0_P127") (pintype "bidirectional"))
    )
    (net (code "127") (name "O2") (class "Default")
      (node (ref "U3") (pin "83") (pinfunction "PD2_83") (pintype "bidirectional"))
      (node (ref "U6") (pin "P131") (pinfunction "IO_L35N_GCLK16_0_P131") (pintype "bidirectional"))
    )
    (net (code "128") (name "O3") (class "Default")
      (node (ref "U3") (pin "84") (pinfunction "PD3_84") (pintype "bidirectional"))
      (node (ref "U6") (pin "P132") (pinfunction "IO_L35P_GCLK17_0_P132") (pintype "bidirectional"))
    )
    (net (code "129") (name "O4") (class "Default")
      (node (ref "U3") (pin "85") (pinfunction "PD4_85") (pintype "bidirectional"))
      (node (ref "U6") (pin "P133") (pinfunction "IO_L34N_GCLK18_0_P133") (pintype "bidirectional"))
    )
    (net (code "130") (name "O5") (class "Default")
      (node (ref "U3") (pin "86") (pinfunction "PD5_86") (pintype "bidirectional"))
      (node (ref "U6") (pin "P137") (pinfunction "IO_L4N_0_P137") (pintype "bidirectional"))
    )
    (net (code "131") (name "O6") (class "Default")
      (node (ref "U3") (pin "87") (pinfunction "PD6_87") (pintype "bidirectional"))
      (node (ref "U6") (pin "P138") (pinfunction "IO_L4P_0_P138") (pintype "bidirectional"))
    )
    (net (code "132") (name "O7") (class "Default")
      (node (ref "U3") (pin "88") (pinfunction "PD7_88") (pintype "bidirectional"))
      (node (ref "U6") (pin "P139") (pinfunction "IO_L3N_0_P139") (pintype "bidirectional"))
    )
    (net (code "133") (name "PA11{slash}USB_DN") (class "Default")
      (node (ref "R26") (pin "2") (pinfunction "2_2") (pintype "passive"))
      (node (ref "U3") (pin "70") (pinfunction "PA11_70") (pintype "bidirectional"))
    )
    (net (code "134") (name "PA12{slash}USB_DP") (class "Default")
      (node (ref "R23") (pin "2") (pinfunction "2_2") (pintype "passive"))
      (node (ref "U3") (pin "71") (pinfunction "PA12_71") (pintype "bidirectional"))
    )
    (net (code "135") (name "PA13{slash}JTMS{slash}SWDIO") (class "Default")
      (node (ref "JP8") (pin "1") (pinfunction "1_1") (pintype "passive"))
      (node (ref "U3") (pin "72") (pinfunction "PA13_72") (pintype "bidirectional"))
    )
    (net (code "136") (name "PA14{slash}JTCK{slash}SWCLK") (class "Default")
      (node (ref "JP8") (pin "3") (pinfunction "3_3") (pintype "passive"))
      (node (ref "U3") (pin "76") (pinfunction "PA14_76") (pintype "bidirectional"))
    )
    (net (code "137") (name "PAGE_A8") (class "Default")
      (node (ref "U3") (pin "24") (pinfunction "PA1_24") (pintype "bidirectional"))
      (node (ref "U6") (pin "P143") (pinfunction "IO_L1N_VREF_0_P143") (pintype "bidirectional"))
    )
    (net (code "138") (name "PB2{slash}BOOT1") (class "Default")
      (node (ref "R16") (pin "2") (pinfunction "2_2") (pintype "passive"))
      (node (ref "R25") (pin "2") (pinfunction "2_2") (pintype "passive"))
      (node (ref "U3") (pin "37") (pinfunction "PB2_37") (pintype "bidirectional"))
    )
    (net (code "139") (name "PS2_CLOCK") (class "Default")
      (node (ref "JP6") (pin "3") (pinfunction "3_3") (pintype "passive"))
      (node (ref "U3") (pin "80") (pinfunction "PC12_80") (pintype "bidirectional"))
    )
    (net (code "140") (name "PS2_DATA") (class "Default")
      (node (ref "JP6") (pin "4") (pinfunction "4_4") (pintype "passive"))
      (node (ref "U3") (pin "79") (pinfunction "PC11_79") (pintype "bidirectional"))
    )
    (net (code "141") (name "RIGHT") (class "Default")
      (node (ref "J2") (pin "4") (pinfunction "4_4") (pintype "passive"))
      (node (ref "U6") (pin "P81") (pinfunction "IO_L46P_1_P81") (pintype "bidirectional"))
    )
    (net (code "142") (name "RST_CTRL_REG") (class "Default")
      (node (ref "U3") (pin "53") (pinfunction "PB14_53") (pintype "bidirectional"))
      (node (ref "U6") (pin "P1") (pinfunction "IO_L83N_VREF_3_P1") (pintype "bidirectional"))
    )
    (net (code "143") (name "RST_DATA_REG") (class "Default")
      (node (ref "U3") (pin "91") (pinfunction "PB5_91") (pintype "bidirectional"))
      (node (ref "U6") (pin "P142") (pinfunction "IO_L2P_0_P142") (pintype "bidirectional"))
    )
    (net (code "144") (name "SCK_LLS") (class "Default")
      (node (ref "MICRO_SD1") (pin "5") (pinfunction "CLK_5") (pintype "bidirectional"))
      (node (ref "R18") (pin "2") (pinfunction "2_2") (pintype "passive"))
    )
    (net (code "145") (name "SCL") (class "Default")
      (node (ref "U3") (pin "92") (pinfunction "PB6_92") (pintype "bidirectional"))
    )
    (net (code "146") (name "SCLK") (class "Default")
      (node (ref "R18") (pin "1") (pinfunction "1_1") (pintype "passive"))
      (node (ref "U3") (pin "30") (pinfunction "PA5_30") (pintype "bidirectional"))
    )
    (net (code "147") (name "SDA") (class "Default")
      (node (ref "U3") (pin "93") (pinfunction "PB7_93") (pintype "bidirectional"))
    )
    (net (code "148") (name "SD_LED") (class "Default")
      (node (ref "LED2") (pin "C") (pinfunction "C_C") (pintype "passive"))
      (node (ref "U3") (pin "15") (pinfunction "PC0_15") (pintype "bidirectional"))
    )
    (net (code "149") (name "SOUND") (class "Default")
      (node (ref "C9") (pin "2") (pinfunction "2_2") (pintype "passive"))
      (node (ref "U3") (pin "29") (pinfunction "PA4_29") (pintype "bidirectional"))
    )
    (net (code "150") (name "SPARE0") (class "Default")
      (node (ref "SJ1") (pin "2") (pinfunction "2_2") (pintype "passive"))
      (node (ref "U3") (pin "77") (pinfunction "PA15_77") (pintype "bidirectional"))
    )
    (net (code "151") (name "SPARE1") (class "Default")
      (node (ref "SJ3") (pin "1") (pinfunction "1_1") (pintype "passive"))
      (node (ref "U3") (pin "25") (pinfunction "PA2_25") (pintype "bidirectional"))
    )
    (net (code "152") (name "SPARE2") (class "Default")
      (node (ref "TP1") (pin "1") (pinfunction "1_1") (pintype "bidirectional"))
      (node (ref "U3") (pin "7") (pinfunction "PC13_7") (pintype "bidirectional"))
    )
    (net (code "153") (name "SS_SD") (class "Default")
      (node (ref "R21") (pin "1") (pinfunction "1_1") (pintype "passive"))
      (node (ref "U3") (pin "54") (pinfunction "PB15_54") (pintype "bidirectional"))
    )
    (net (code "154") (name "TCK") (class "Default")
      (node (ref "JP3") (pin "1") (pinfunction "1_1") (pintype "passive"))
      (node (ref "U6") (pin "P109") (pinfunction "TCK_P109") (pintype "bidirectional"))
    )
    (net (code "155") (name "TDI") (class "Default")
      (node (ref "JP3") (pin "3") (pinfunction "3_3") (pintype "passive"))
      (node (ref "U6") (pin "P110") (pinfunction "TDI_P110") (pintype "bidirectional"))
    )
    (net (code "156") (name "TDO") (class "Default")
      (node (ref "JP3") (pin "2") (pinfunction "2_2") (pintype "passive"))
      (node (ref "U6") (pin "P106") (pinfunction "TDO_P106") (pintype "bidirectional"))
    )
    (net (code "157") (name "TMS") (class "Default")
      (node (ref "JP3") (pin "4") (pinfunction "4_4") (pintype "passive"))
      (node (ref "U6") (pin "P107") (pinfunction "TMS_P107") (pintype "bidirectional"))
    )
    (net (code "158") (name "UART_RX") (class "Default")
      (node (ref "JP4") (pin "3") (pinfunction "3_3") (pintype "passive"))
      (node (ref "U3") (pin "69") (pinfunction "PA10_69") (pintype "bidirectional"))
    )
    (net (code "159") (name "UART_TX") (class "Default")
      (node (ref "JP4") (pin "4") (pinfunction "4_4") (pintype "passive"))
      (node (ref "U3") (pin "68") (pinfunction "PA9_68") (pintype "bidirectional"))
    )
    (net (code "160") (name "UP") (class "Default")
      (node (ref "J2") (pin "1") (pinfunction "1_1") (pintype "passive"))
      (node (ref "U6") (pin "P78") (pinfunction "IO_L47N_1_P78") (pintype "bidirectional"))
    )
    (net (code "161") (name "VCC") (class "Default")
      (node (ref "23B") (pin "1") (pinfunction "P_1") (pintype "passive"))
      (node (ref "2A") (pin "1") (pinfunction "P_1") (pintype "passive"))
      (node (ref "C3") (pin "1") (pinfunction "1_1") (pintype "passive"))
      (node (ref "D2") (pin "C") (pinfunction "C_C") (pintype "passive"))
      (node (ref "D4") (pin "C") (pinfunction "C_C") (pintype "passive"))
      (node (ref "IC2") (pin "3") (pinfunction "VIN_3") (pintype "input"))
      (node (ref "IC3") (pin "1") (pinfunction "DIR_1") (pintype "input"))
      (node (ref "IC5") (pin "3") (pinfunction "VIN_3") (pintype "input"))
      (node (ref "JP4") (pin "1") (pinfunction "1_1") (pintype "passive"))
      (node (ref "JP6") (pin "1") (pinfunction "1_1") (pintype "passive"))
      (node (ref "R11") (pin "1") (pinfunction "1_1") (pintype "passive"))
      (node (ref "R15") (pin "2") (pinfunction "2_2") (pintype "passive"))
      (node (ref "R22") (pin "2") (pinfunction "2_2") (pintype "passive"))
      (node (ref "R6") (pin "2") (pinfunction "2_2") (pintype "passive"))
      (node (ref "U2") (pin "32") (pinfunction "VCC_32") (pintype "power_in"))
    )
    (net (code "162") (name "VCC_USB") (class "Default")
      (node (ref "D2") (pin "A") (pinfunction "A_A") (pintype "passive"))
      (node (ref "J3") (pin "A4_B9") (pinfunction "VBUS_A4_B9") (pintype "power_in"))
      (node (ref "J3") (pin "B4_A9") (pinfunction "VBUS_B4_A9") (pintype "power_in"))
    )
    (net (code "163") (name "V_BLUE") (class "Default")
      (node (ref "R29") (pin "1") (pinfunction "1_1") (pintype "passive"))
      (node (ref "U6") (pin "P9") (pinfunction "IO_L50N_3_P9") (pintype "bidirectional"))
    )
    (net (code "164") (name "V_BLUE'") (class "Default")
      (node (ref "R28") (pin "1") (pinfunction "1_1") (pintype "passive"))
      (node (ref "R29") (pin "2") (pinfunction "2_2") (pintype "passive"))
      (node (ref "R33") (pin "2") (pinfunction "2_2") (pintype "passive"))
      (node (ref "X1") (pin "7") (pinfunction "7_7") (pintype "passive"))
    )
    (net (code "165") (name "V_GREEN") (class "Default")
      (node (ref "R31") (pin "1") (pinfunction "1_1") (pintype "passive"))
      (node (ref "U6") (pin "P8") (pinfunction "IO_L51P_3_P8") (pintype "bidirectional"))
    )
    (net (code "166") (name "V_GREEN'") (class "Default")
      (node (ref "R27") (pin "1") (pinfunction "1_1") (pintype "passive"))
      (node (ref "R31") (pin "2") (pinfunction "2_2") (pintype "passive"))
      (node (ref "R34") (pin "2") (pinfunction "2_2") (pintype "passive"))
      (node (ref "X1") (pin "11") (pinfunction "11_11") (pintype "passive"))
    )
    (net (code "167") (name "V_RED") (class "Default")
      (node (ref "R32") (pin "1") (pinfunction "1_1") (pintype "passive"))
      (node (ref "U6") (pin "P7") (pinfunction "IO_L51N_3_P7") (pintype "bidirectional"))
    )
    (net (code "168") (name "V_RED'") (class "Default")
      (node (ref "R19") (pin "1") (pinfunction "1_1") (pintype "passive"))
      (node (ref "R32") (pin "2") (pinfunction "2_2") (pintype "passive"))
      (node (ref "R35") (pin "2") (pinfunction "2_2") (pintype "passive"))
      (node (ref "X1") (pin "15") (pinfunction "15_15") (pintype "passive"))
    )
    (net (code "169") (name "unconnected-(IC3A-A1-Pad2)") (class "Default")
      (node (ref "IC3") (pin "2") (pinfunction "A1_2") (pintype "bidirectional"))
    )
    (net (code "170") (name "unconnected-(IC3A-A7-Pad8)") (class "Default")
      (node (ref "IC3") (pin "8") (pinfunction "A7_8") (pintype "bidirectional"))
    )
    (net (code "171") (name "unconnected-(IC3A-A8-Pad9)") (class "Default")
      (node (ref "IC3") (pin "9") (pinfunction "A8_9") (pintype "bidirectional"))
    )
    (net (code "172") (name "unconnected-(IC3A-B1-Pad18)") (class "Default")
      (node (ref "IC3") (pin "18") (pinfunction "B1_18") (pintype "bidirectional"))
    )
    (net (code "173") (name "unconnected-(IC3A-B7-Pad12)") (class "Default")
      (node (ref "IC3") (pin "12") (pinfunction "B7_12") (pintype "bidirectional"))
    )
    (net (code "174") (name "unconnected-(IC3A-B8-Pad11)") (class "Default")
      (node (ref "IC3") (pin "11") (pinfunction "B8_11") (pintype "bidirectional"))
    )
    (net (code "175") (name "unconnected-(J2-Pad5)") (class "Default")
      (node (ref "J2") (pin "5") (pinfunction "5_5") (pintype "passive"))
    )
    (net (code "176") (name "unconnected-(J2-Pad7)") (class "Default")
      (node (ref "J2") (pin "7") (pinfunction "7_7") (pintype "passive"))
    )
    (net (code "177") (name "unconnected-(J2-Pad9)") (class "Default")
      (node (ref "J2") (pin "9") (pinfunction "9_9") (pintype "passive"))
    )
    (net (code "178") (name "unconnected-(MICRO_SD1-CD-PadCD1)") (class "Default")
      (node (ref "MICRO_SD1") (pin "CD1") (pinfunction "CD_CD1") (pintype "passive"))
    )
    (net (code "179") (name "unconnected-(MICRO_SD1-DAT1-Pad8)") (class "Default")
      (node (ref "MICRO_SD1") (pin "8") (pinfunction "DAT1_8") (pintype "bidirectional"))
    )
    (net (code "180") (name "unconnected-(MICRO_SD1-DAT2-Pad1)") (class "Default")
      (node (ref "MICRO_SD1") (pin "1") (pinfunction "DAT2_1") (pintype "bidirectional"))
    )
    (net (code "181") (name "unconnected-(Q1-TS-Pad1)") (class "Default")
      (node (ref "Q1") (pin "1") (pinfunction "TS_1") (pintype "passive"))
    )
    (net (code "182") (name "unconnected-(U3-PC4-Pad33)") (class "Default")
      (node (ref "U3") (pin "33") (pinfunction "PC4_33") (pintype "bidirectional"))
    )
    (net (code "183") (name "unconnected-(U3-PC5-Pad34)") (class "Default")
      (node (ref "U3") (pin "34") (pinfunction "PC5_34") (pintype "bidirectional"))
    )
    (net (code "184") (name "unconnected-(U6-CMPCS_B_2-PadP72)") (class "Default")
      (node (ref "U6") (pin "P72") (pinfunction "CMPCS_B_2_P72") (pintype "bidirectional"))
    )
    (net (code "185") (name "unconnected-(X1-Pad2)") (class "Default")
      (node (ref "X1") (pin "2") (pinfunction "2_2") (pintype "passive"))
    )
    (net (code "186") (name "unconnected-(X1-Pad6)") (class "Default")
      (node (ref "X1") (pin "6") (pinfunction "6_6") (pintype "passive"))
    )
    (net (code "187") (name "unconnected-(X1-Pad10)") (class "Default")
      (node (ref "X1") (pin "10") (pinfunction "10_10") (pintype "passive"))
    )
    (net (code "188") (name "unconnected-(X1-Pad12)") (class "Default")
      (node (ref "X1") (pin "12") (pinfunction "12_12") (pintype "passive"))
    )
    (net (code "189") (name "unconnected-(X1-Pad20)") (class "Default")
      (node (ref "X1") (pin "20") (pinfunction "20_20") (pintype "passive"))
    )
    (net (code "190") (name "{slash}BUSAK") (class "Default")
      (node (ref "18A") (pin "1") (pinfunction "P_1") (pintype "passive"))
      (node (ref "SJ4") (pin "2") (pinfunction "2_2") (pintype "passive"))
    )
    (net (code "191") (name "{slash}BUSRQ") (class "Default")
      (node (ref "20A") (pin "1") (pinfunction "P_1") (pintype "passive"))
      (node (ref "SJ2") (pin "2") (pinfunction "2_2") (pintype "passive"))
    )
    (net (code "192") (name "{slash}BUSRQ'") (class "Default")
      (node (ref "SJ2") (pin "1") (pinfunction "1_1") (pintype "passive"))
      (node (ref "U6") (pin "P75") (pinfunction "IO_L74P_AWAKE_1_P75") (pintype "bidirectional"))
    )
    (net (code "193") (name "{slash}CLOCK") (class "Default")
      (node (ref "6B") (pin "1") (pinfunction "P_1") (pintype "passive"))
      (node (ref "U6") (pin "P24") (pinfunction "IO_L41P_GCLK27_3_P24") (pintype "bidirectional"))
    )
    (net (code "194") (name "{slash}HALT") (class "Default")
      (node (ref "13A") (pin "1") (pinfunction "P_1") (pintype "passive"))
      (node (ref "U6") (pin "P45") (pinfunction "IO_L49N_D4_2_P45") (pintype "bidirectional"))
    )
    (net (code "195") (name "{slash}IORQ") (class "Default")
      (node (ref "IC3") (pin "14") (pinfunction "B5_14") (pintype "bidirectional"))
      (node (ref "U6") (pin "P51") (pinfunction "IO_L31P_GCLK31_D14_2_P51") (pintype "bidirectional"))
    )
    (net (code "196") (name "{slash}IORQ_5") (class "Default")
      (node (ref "15A") (pin "1") (pinfunction "P_1") (pintype "passive"))
      (node (ref "IC3") (pin "6") (pinfunction "A5_6") (pintype "bidirectional"))
    )
    (net (code "197") (name "{slash}M1") (class "Default")
      (node (ref "IC3") (pin "17") (pinfunction "B2_17") (pintype "bidirectional"))
      (node (ref "U6") (pin "P67") (pinfunction "IO_L2P_CMPCLK_2_P67") (pintype "bidirectional"))
    )
    (net (code "198") (name "{slash}M1_5") (class "Default")
      (node (ref "22A") (pin "1") (pinfunction "P_1") (pintype "passive"))
      (node (ref "IC3") (pin "3") (pinfunction "A2_3") (pintype "bidirectional"))
    )
    (net (code "199") (name "{slash}MEM_OE") (class "Default")
      (node (ref "U2") (pin "24") (pinfunction "OE_24") (pintype "input"))
      (node (ref "U3") (pin "67") (pinfunction "PA8_67") (pintype "bidirectional"))
      (node (ref "U6") (pin "P92") (pinfunction "IO_L41N_GCLK8_1_P92") (pintype "bidirectional"))
    )
    (net (code "200") (name "{slash}MREQ") (class "Default")
      (node (ref "IC3") (pin "13") (pinfunction "B6_13") (pintype "bidirectional"))
      (node (ref "U6") (pin "P47") (pinfunction "IO_L48N_RDWR_B_VREF_2_P47") (pintype "bidirectional"))
    )
    (net (code "201") (name "{slash}MREQ_5") (class "Default")
      (node (ref "14A") (pin "1") (pinfunction "P_1") (pintype "passive"))
      (node (ref "IC3") (pin "7") (pinfunction "A6_7") (pintype "bidirectional"))
    )
    (net (code "202") (name "{slash}NMI") (class "Default")
      (node (ref "12A") (pin "1") (pinfunction "P_1") (pintype "passive"))
    )
    (net (code "203") (name "{slash}OE_OL") (class "Default")
      (node (ref "U3") (pin "47") (pinfunction "PB10_47") (pintype "bidirectional"))
      (node (ref "U6") (pin "P12") (pinfunction "IO_L49P_3_P12") (pintype "bidirectional"))
    )
    (net (code "204") (name "{slash}RD") (class "Default")
      (node (ref "IC3") (pin "15") (pinfunction "B4_15") (pintype "bidirectional"))
      (node (ref "U6") (pin "P105") (pinfunction "IO_L1P_1_P105") (pintype "bidirectional"))
    )
    (net (code "205") (name "{slash}RD_5") (class "Default")
      (node (ref "16A") (pin "1") (pinfunction "P_1") (pintype "passive"))
      (node (ref "IC3") (pin "5") (pinfunction "A4_5") (pintype "bidirectional"))
    )
    (net (code "206") (name "{slash}RESET") (class "Default")
      (node (ref "21A") (pin "1") (pinfunction "P_1") (pintype "passive"))
      (node (ref "U3") (pin "96") (pinfunction "PB9_96") (pintype "bidirectional"))
    )
    (net (code "207") (name "{slash}RESET_FPGA") (class "Default")
      (node (ref "U3") (pin "95") (pinfunction "PB8_95") (pintype "bidirectional"))
      (node (ref "U6") (pin "P140") (pinfunction "IO_L3P_0_P140") (pintype "bidirectional"))
    )
    (net (code "208") (name "{slash}RFSH") (class "Default")
      (node (ref "23A") (pin "1") (pinfunction "P_1") (pintype "passive"))
      (node (ref "U6") (pin "P74") (pinfunction "IO_L74N_DOUT_BUSY_1_P74") (pintype "bidirectional"))
    )
    (net (code "209") (name "{slash}WAIT") (class "Default")
      (node (ref "19A") (pin "1") (pinfunction "P_1") (pintype "passive"))
      (node (ref "U3") (pin "23") (pinfunction "PA0_23") (pintype "bidirectional"))
    )
    (net (code "210") (name "{slash}WR") (class "Default")
      (node (ref "IC3") (pin "16") (pinfunction "B3_16") (pintype "bidirectional"))
      (node (ref "U6") (pin "P58") (pinfunction "IO_L14P_D11_2_P58") (pintype "bidirectional"))
    )
    (net (code "211") (name "{slash}WR'") (class "Default")
      (node (ref "U2") (pin "29") (pinfunction "WE_29") (pintype "input"))
      (node (ref "U3") (pin "26") (pinfunction "PA3_26") (pintype "bidirectional"))
      (node (ref "U6") (pin "P102") (pinfunction "IO_L32P_1_P102") (pintype "bidirectional"))
    )
    (net (code "212") (name "{slash}WR_5") (class "Default")
      (node (ref "17A") (pin "1") (pinfunction "P_1") (pintype "passive"))
      (node (ref "IC3") (pin "4") (pinfunction "A3_4") (pintype "bidirectional"))
    )
    (net (code "213") (name "~{RESET}") (class "Default")
      (node (ref "C5") (pin "2") (pinfunction "2_2") (pintype "passive"))
      (node (ref "R15") (pin "1") (pinfunction "1_1") (pintype "passive"))
      (node (ref "S1") (pin "2") (pinfunction "S_2") (pintype "passive"))
      (node (ref "U3") (pin "14") (pinfunction "NRST_14") (pintype "bidirectional"))
    )
  )
)
